# LED_matrix.net
KiCad netlist of a schematic drawn in EAGLE
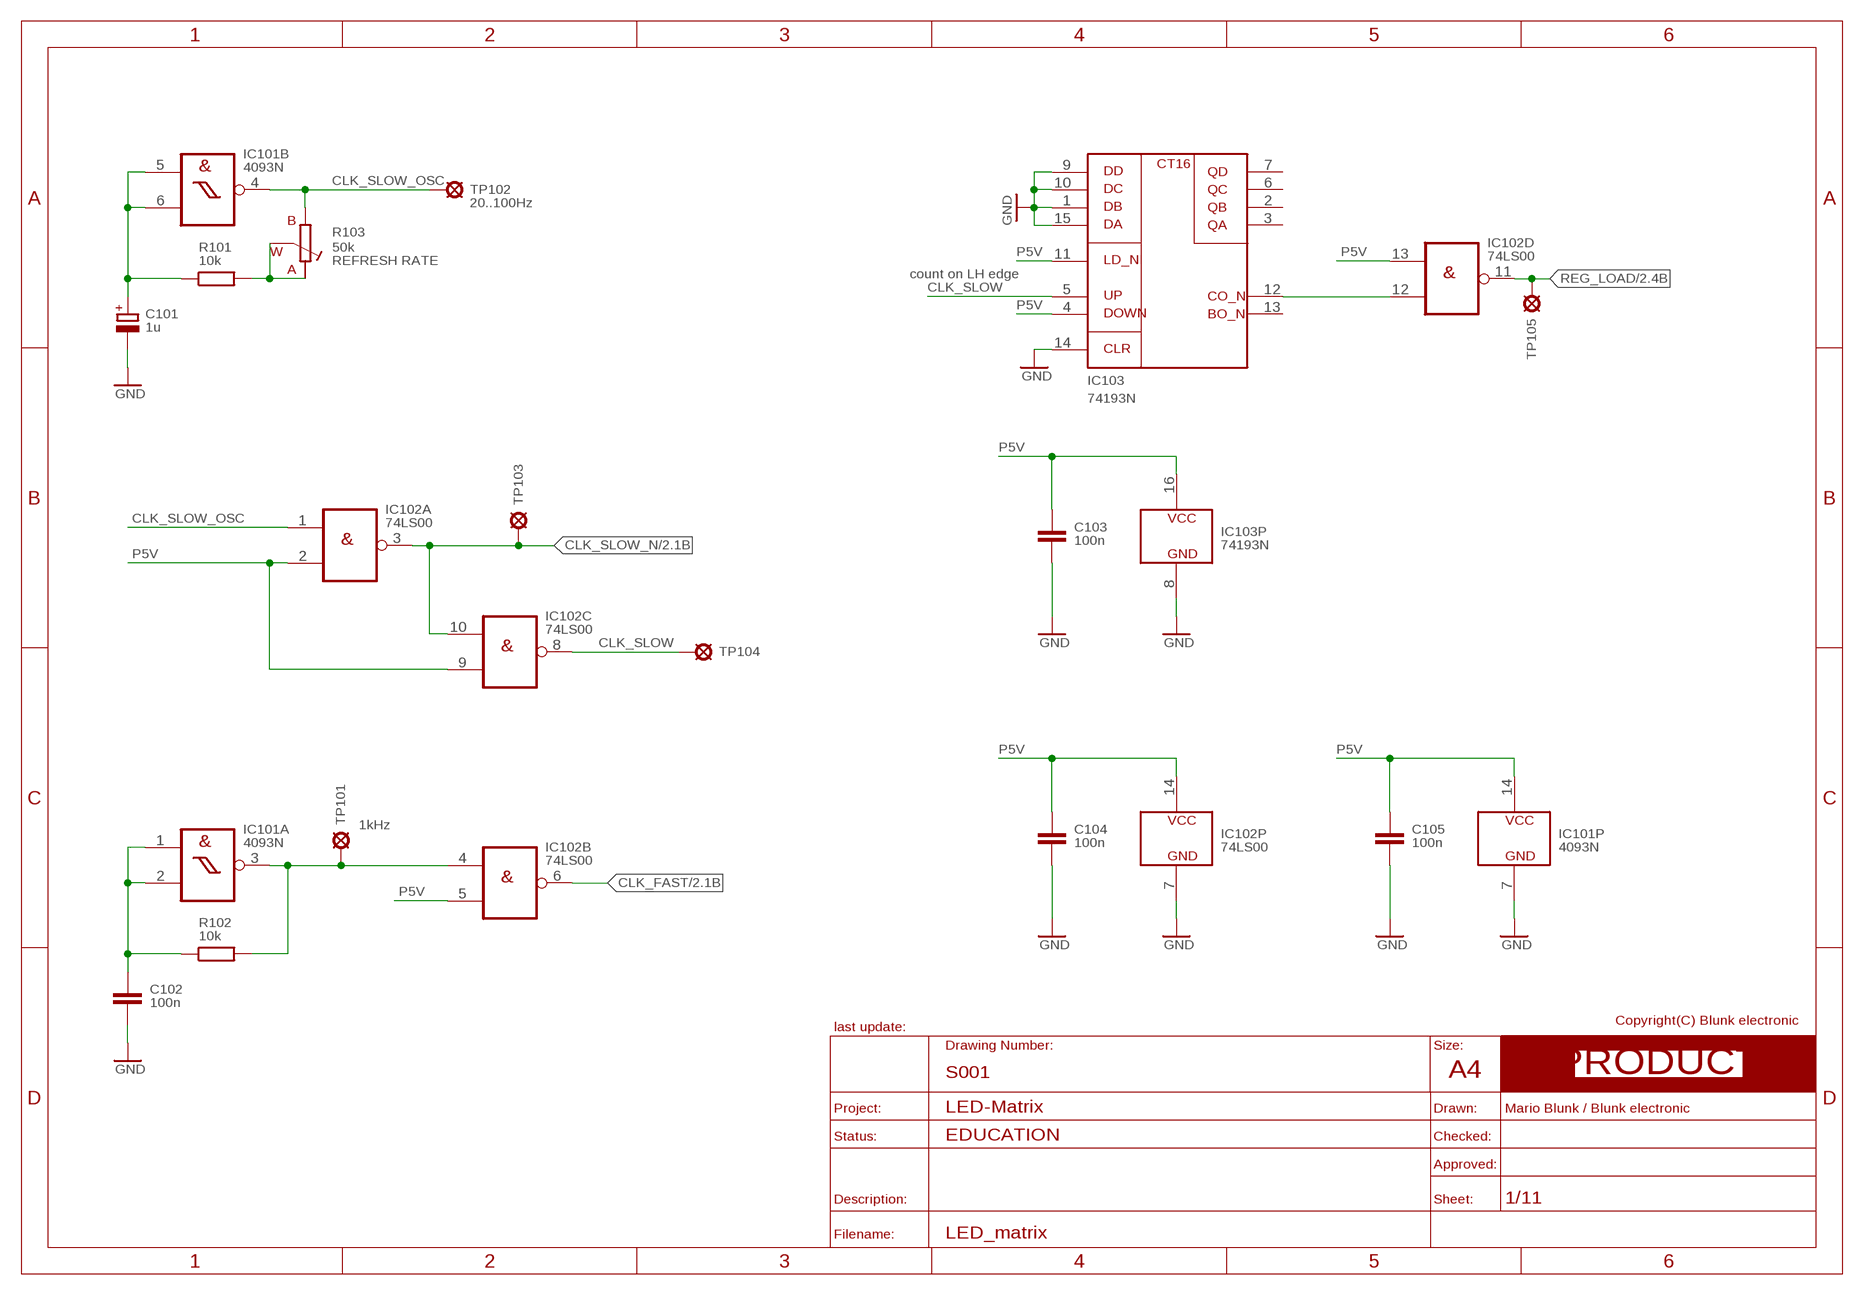
[diagram p0: schematic, sheet 1]
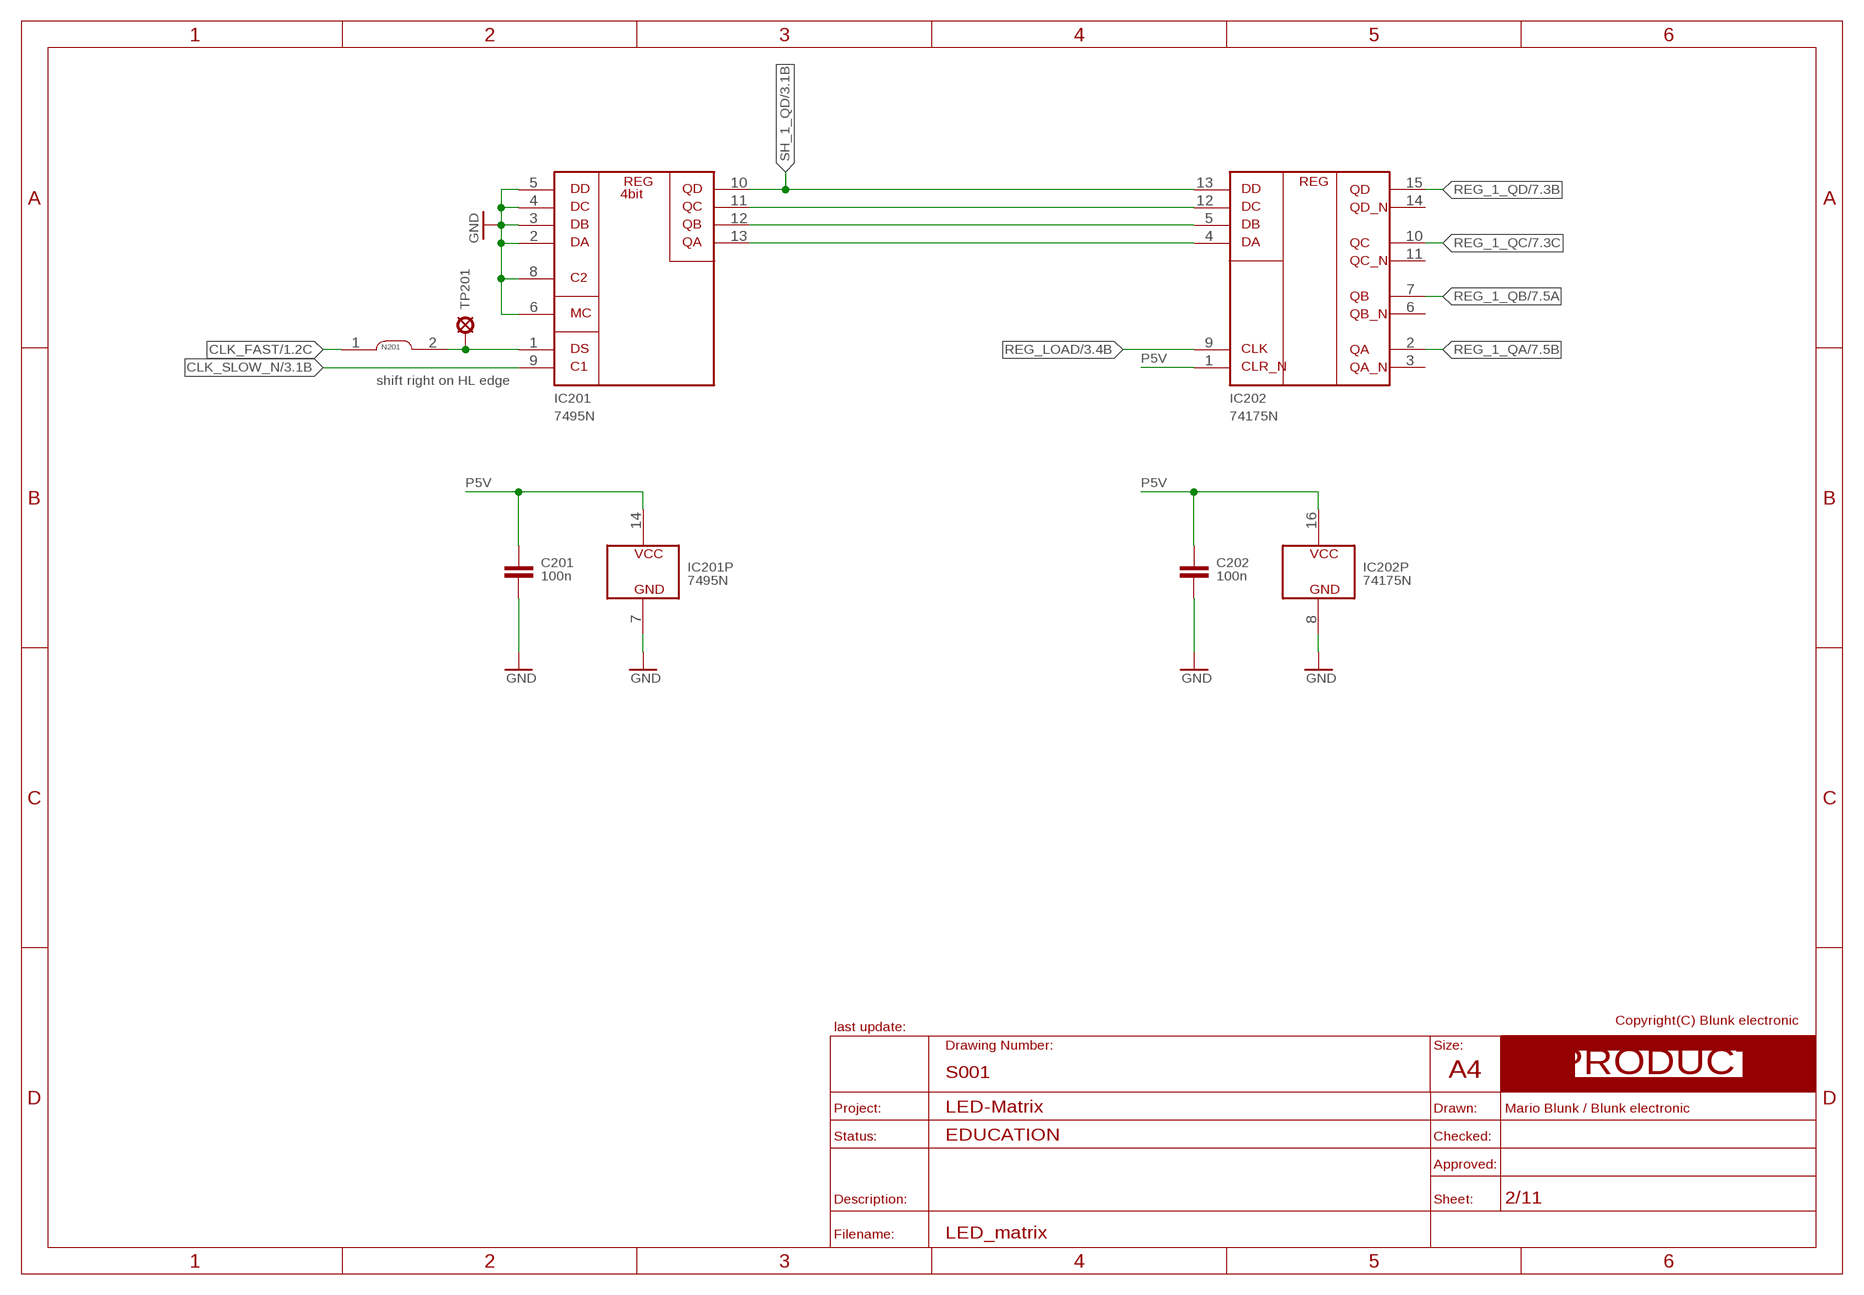
[diagram p1: schematic, sheet 2]
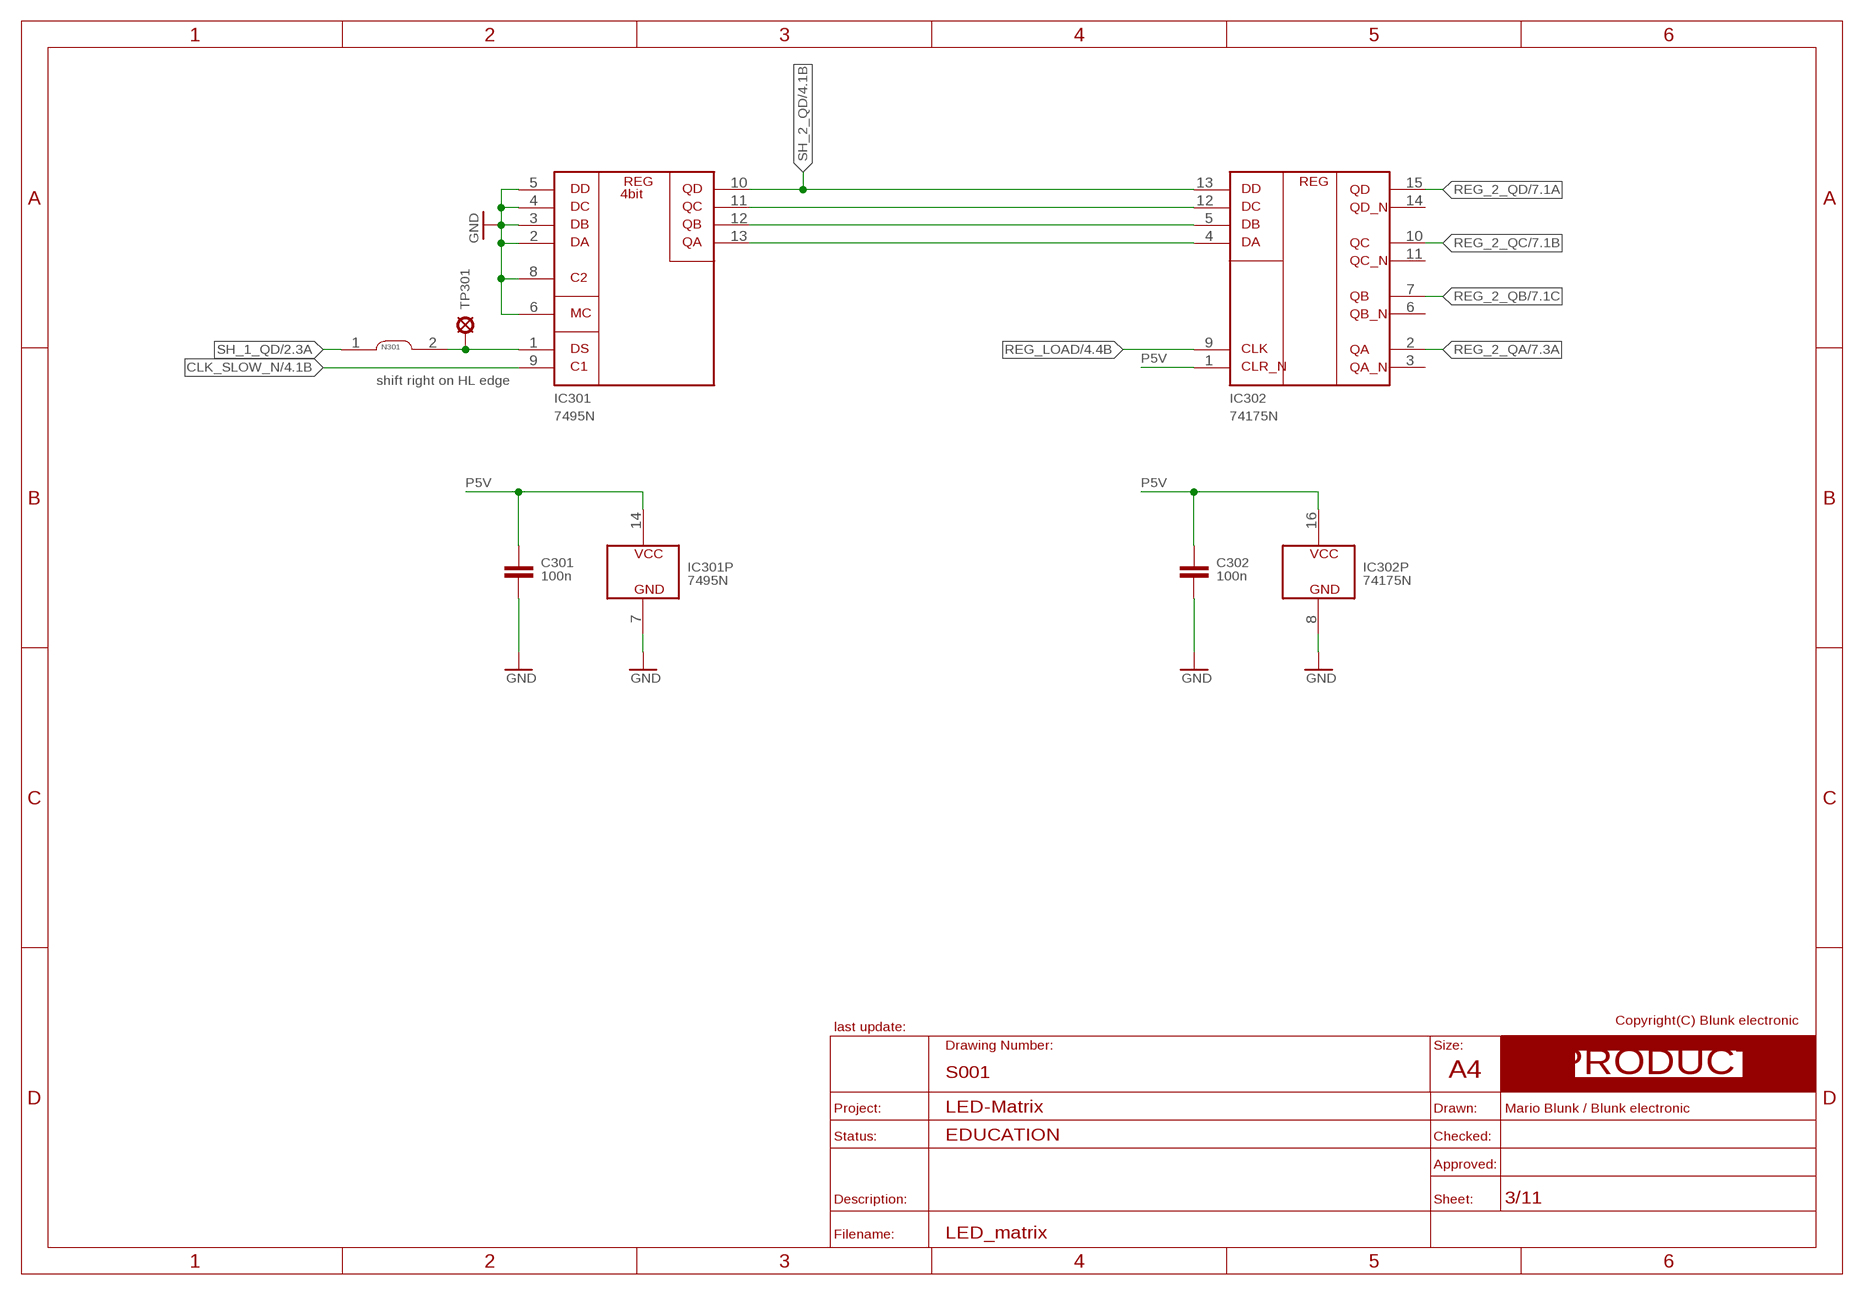
[diagram p2: schematic, sheet 3]
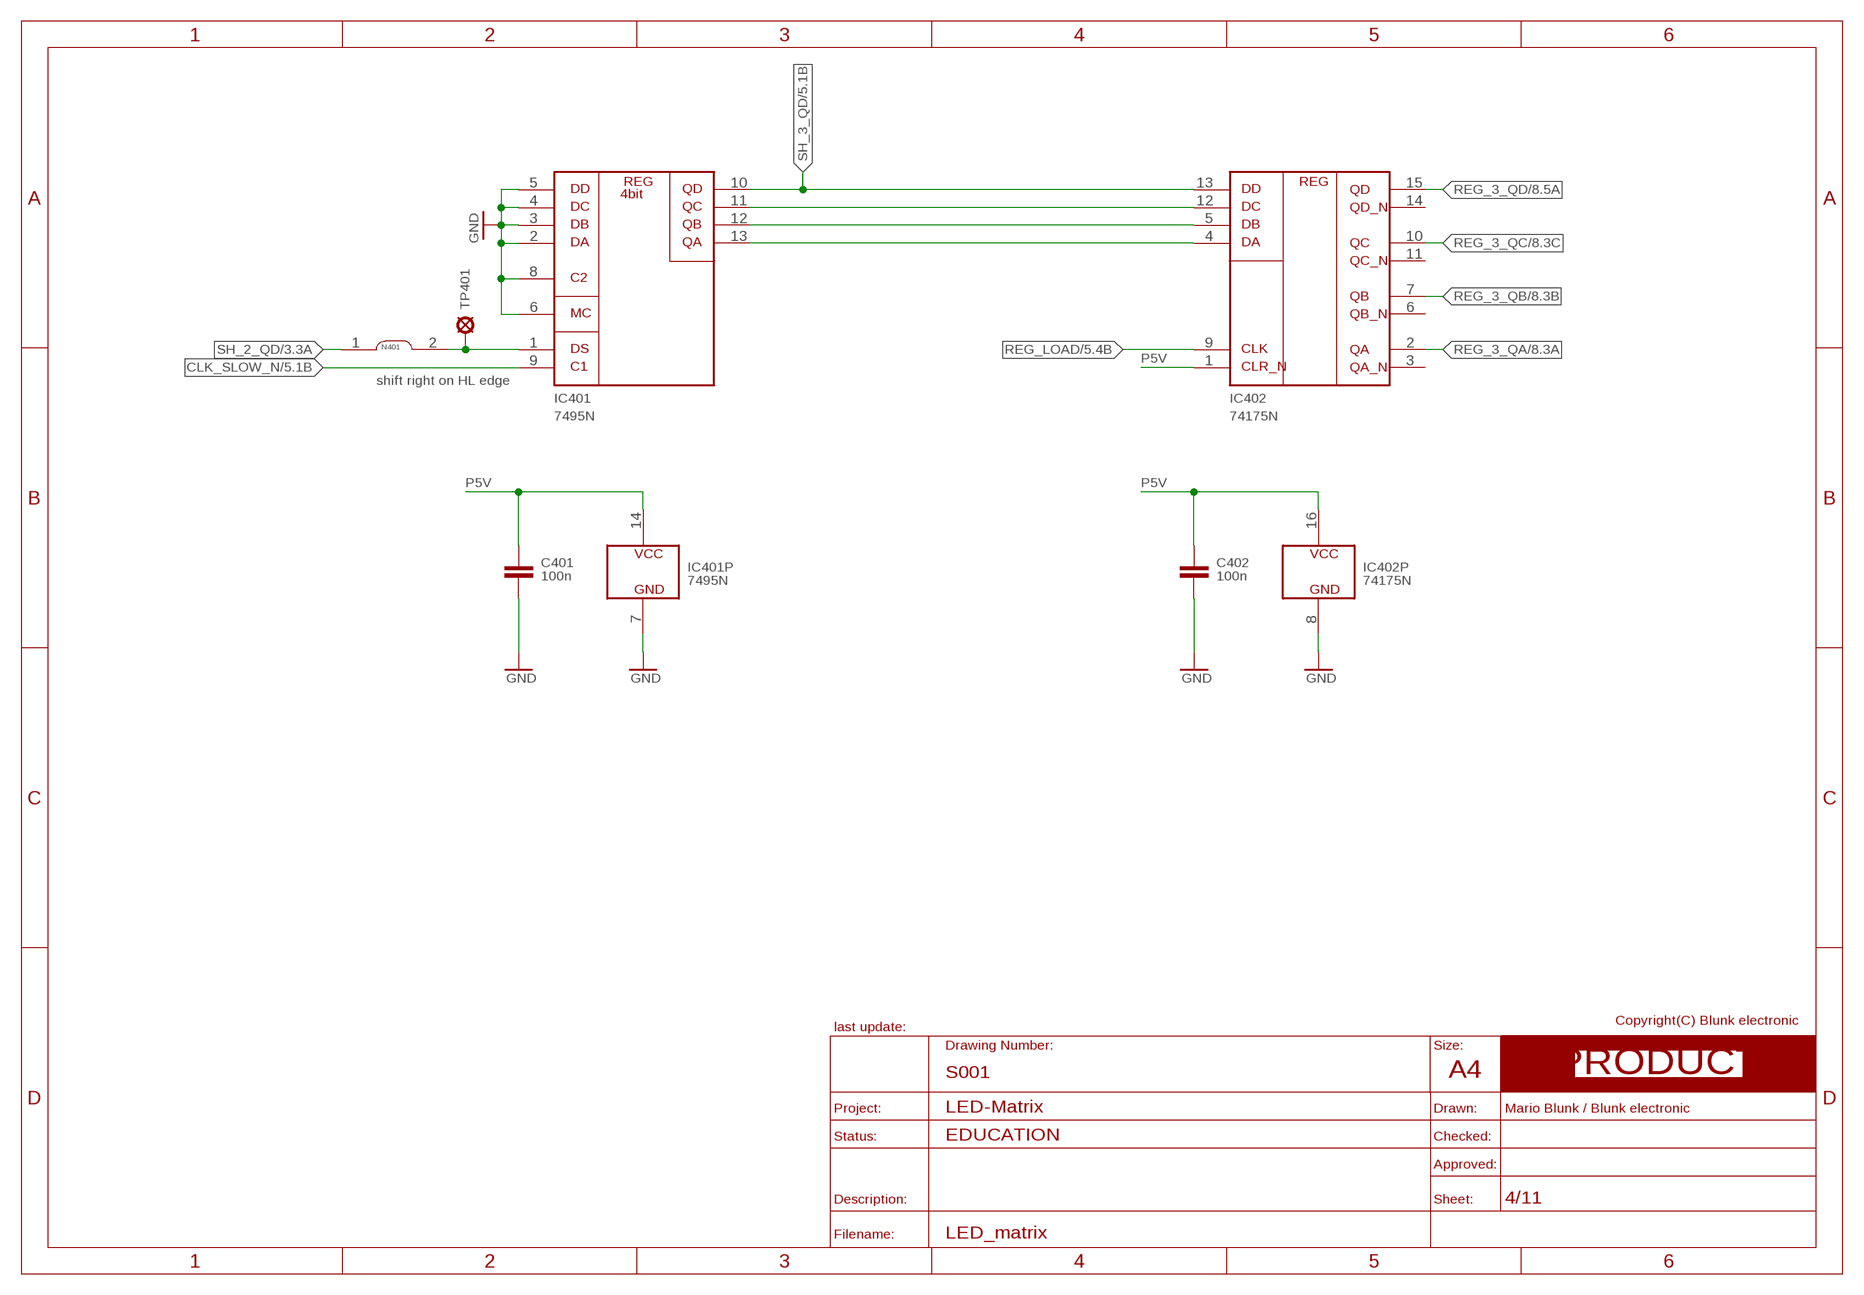
[diagram p3: schematic, sheet 4]
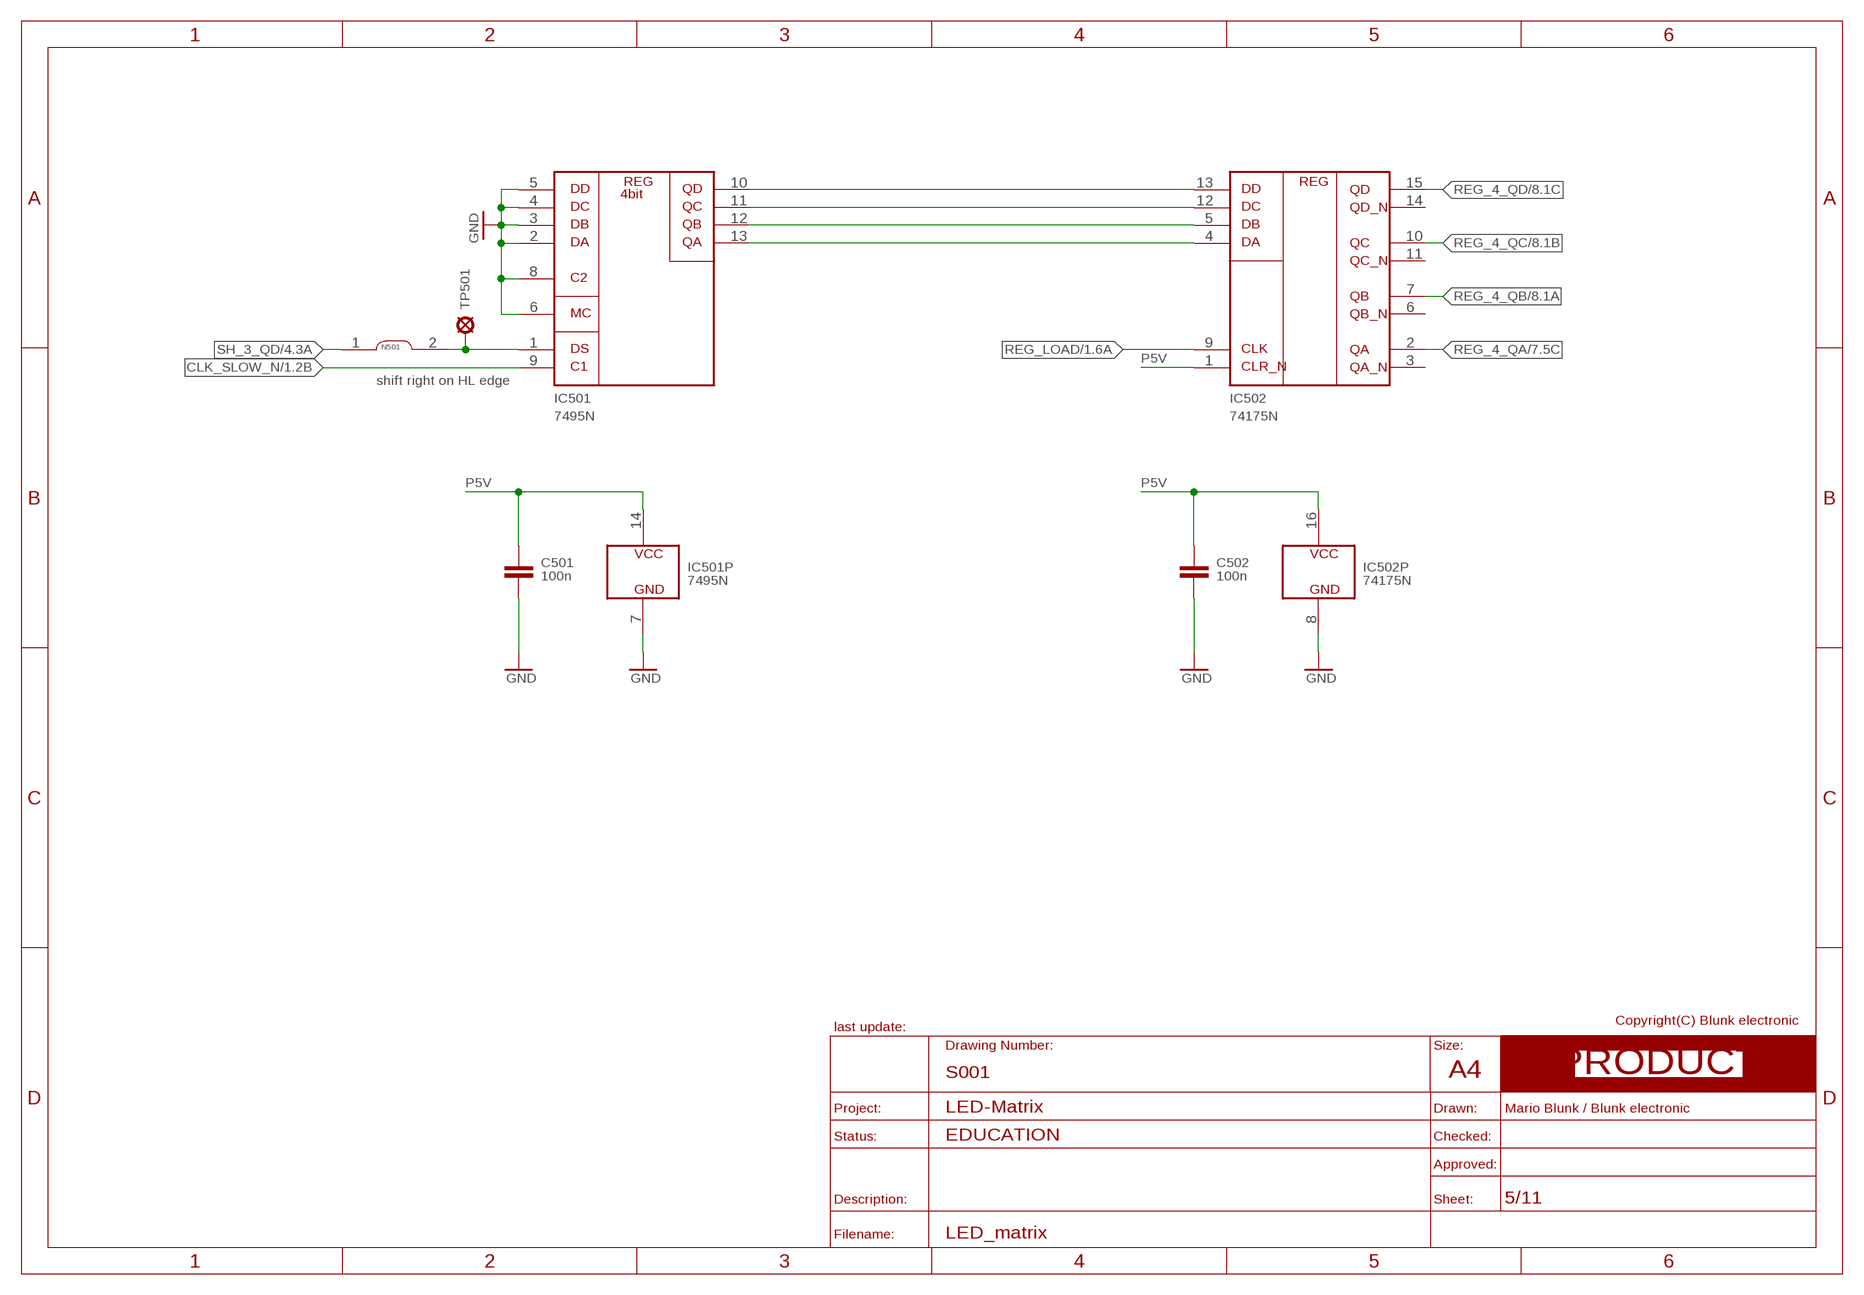
[diagram p4: schematic, sheet 5]
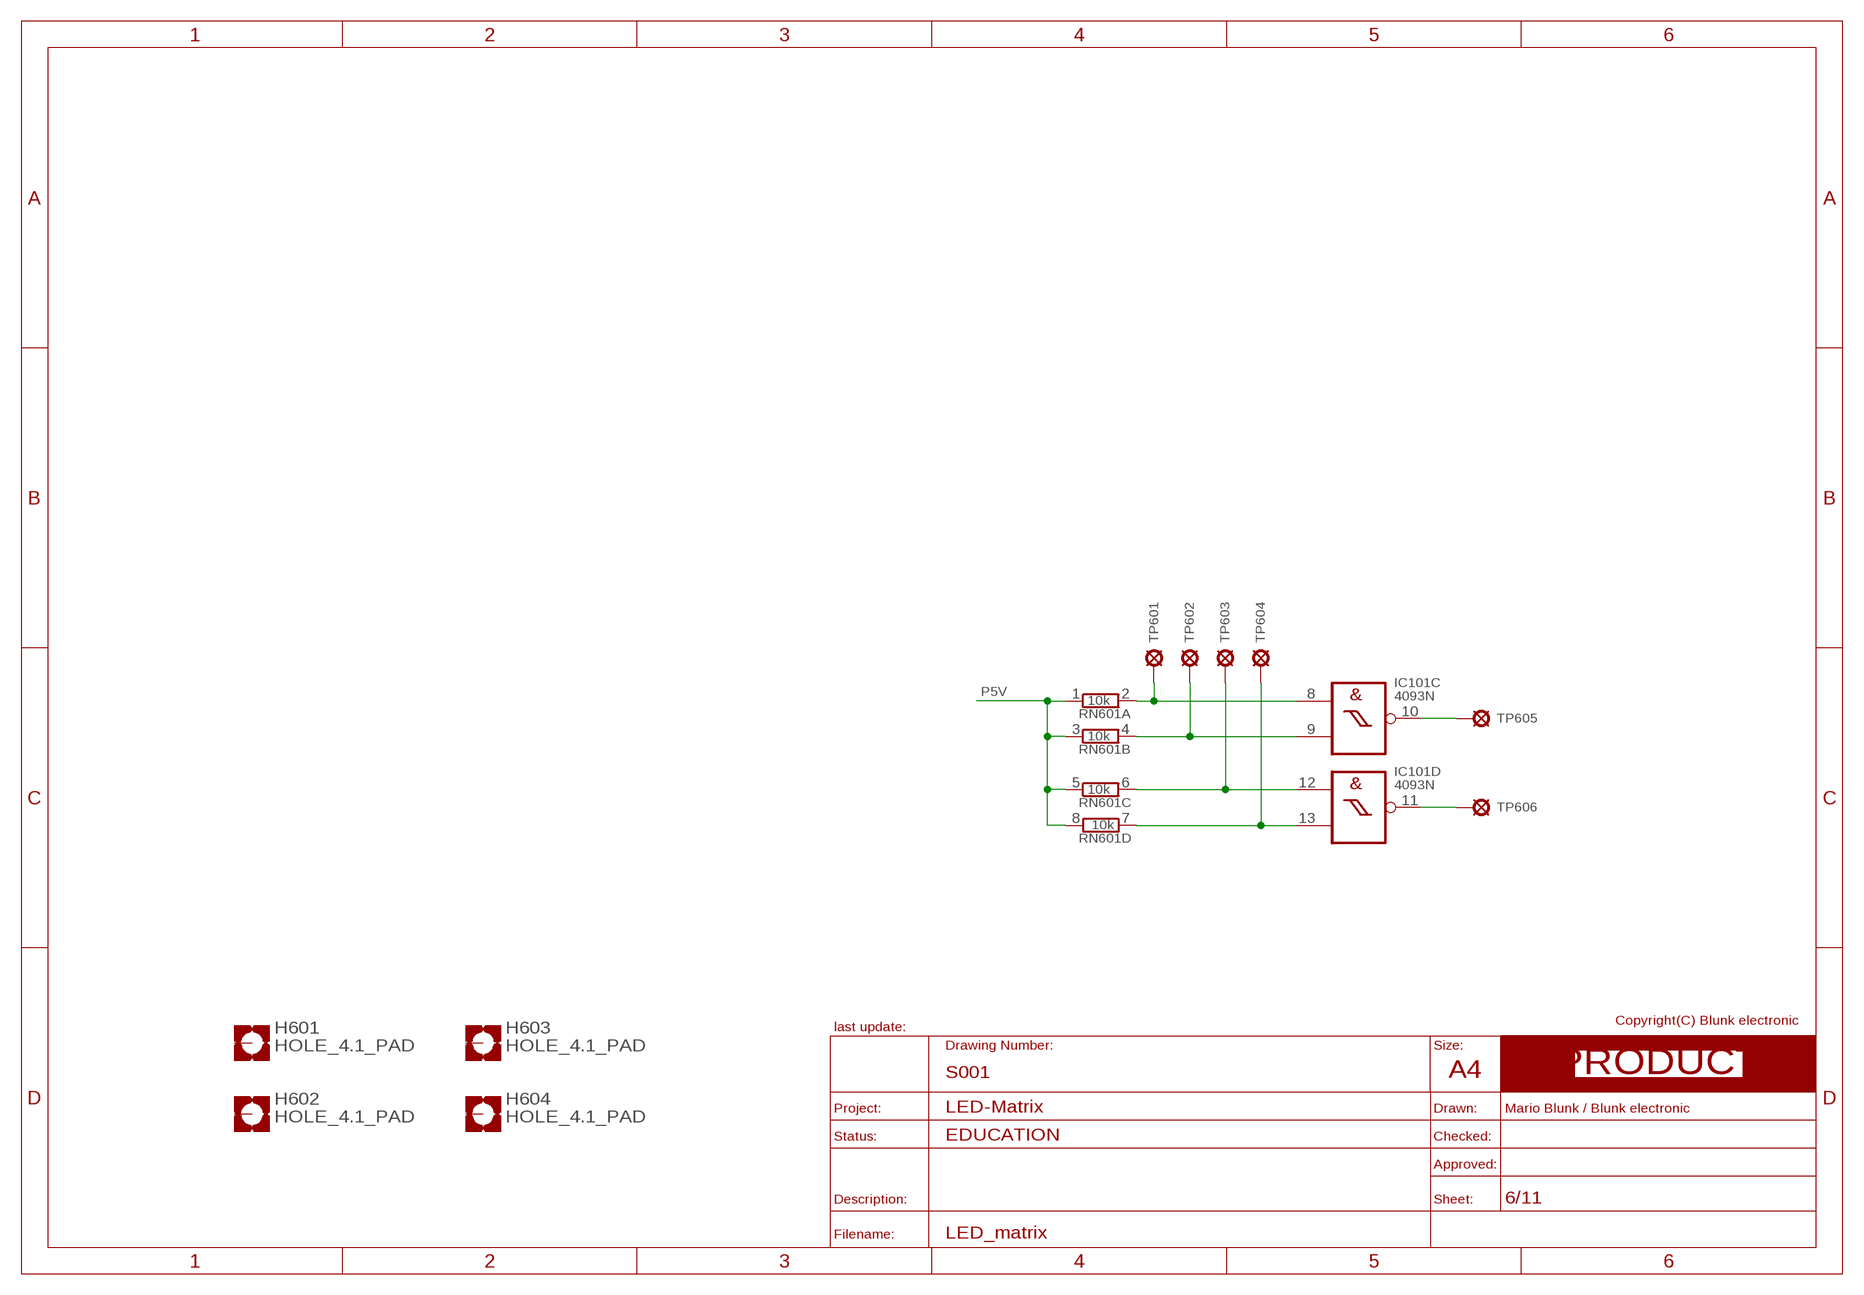
[diagram p5: schematic, sheet 6]
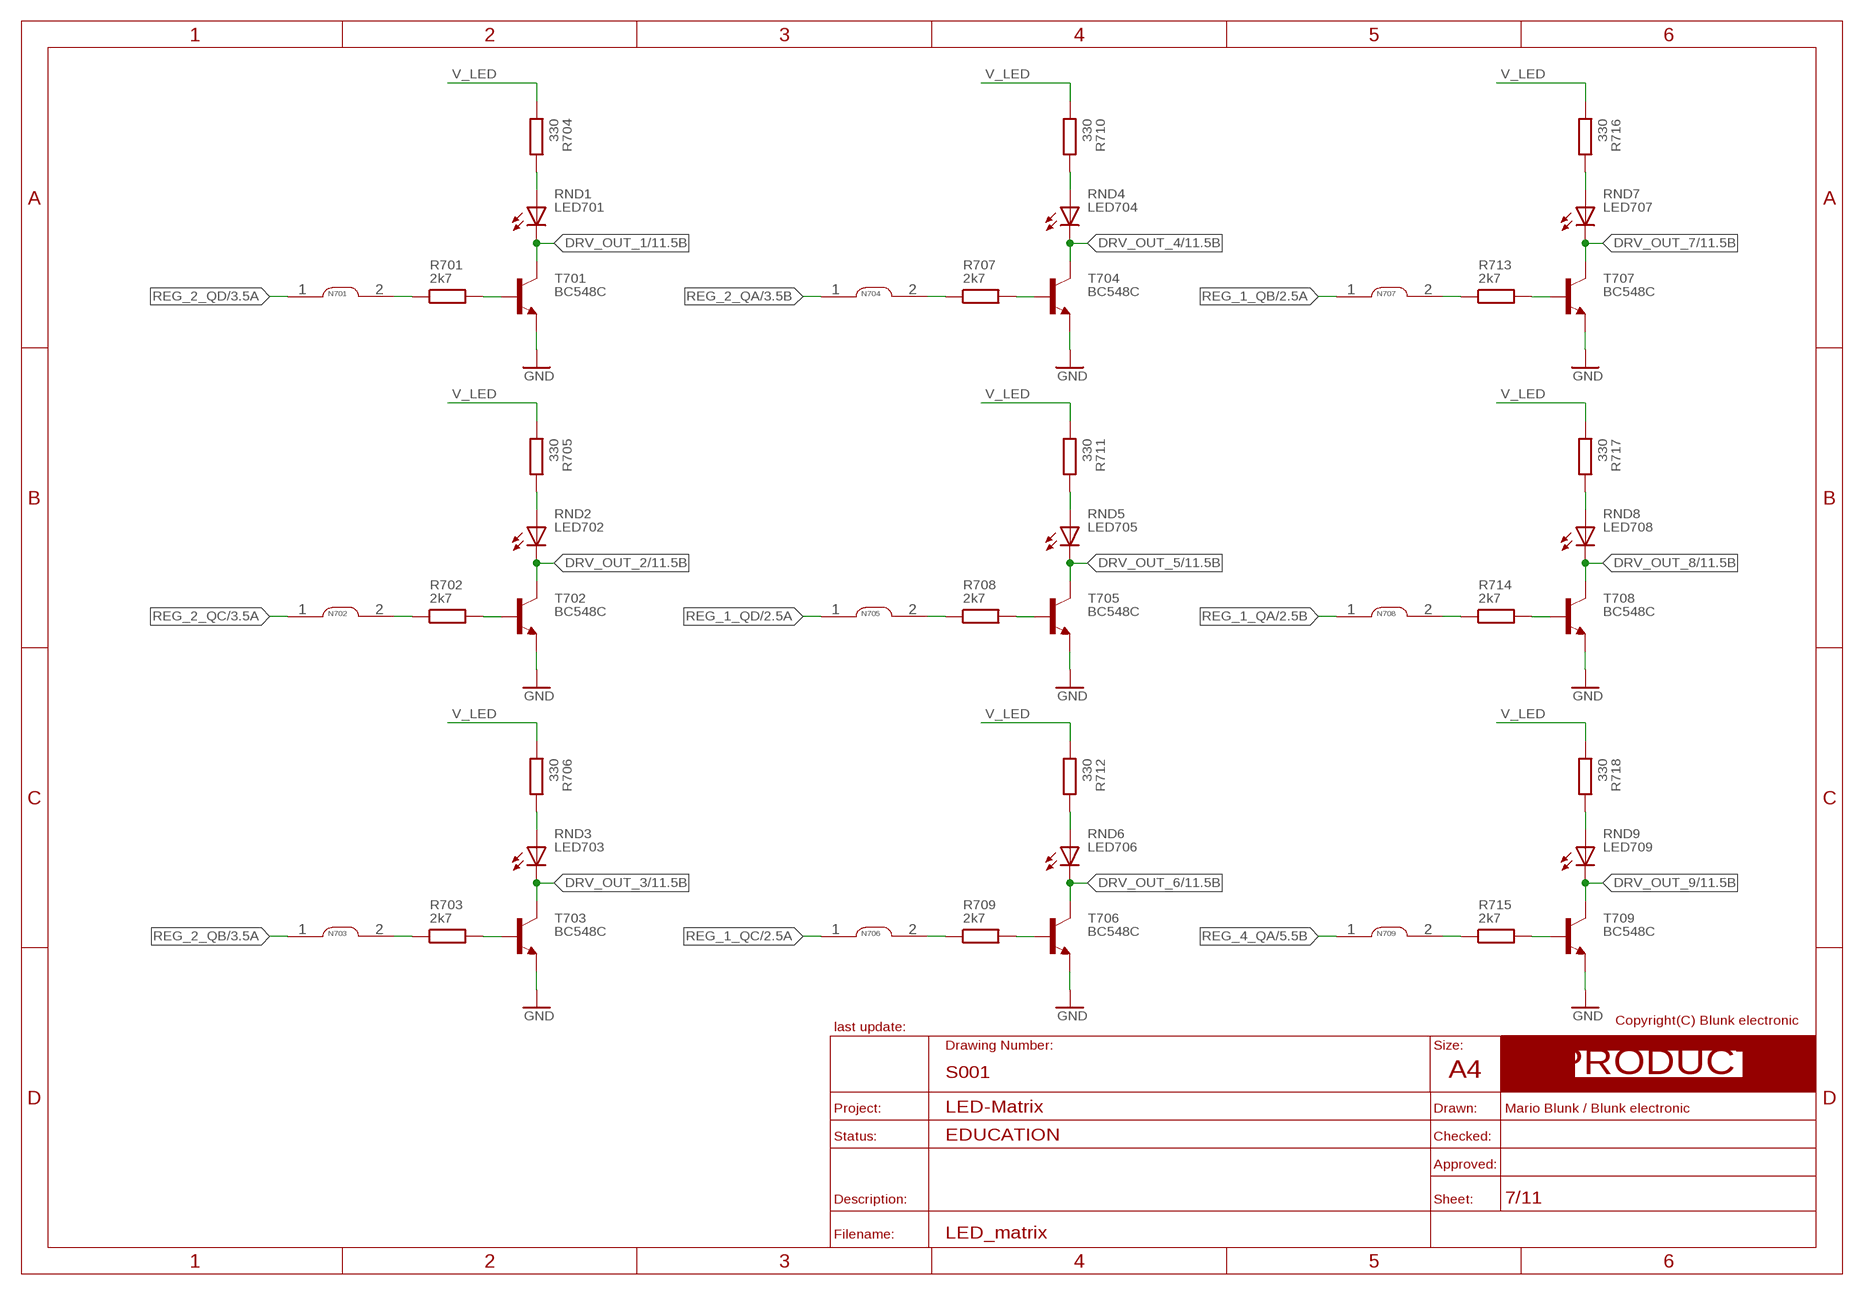
[diagram p6: schematic, sheet 7]
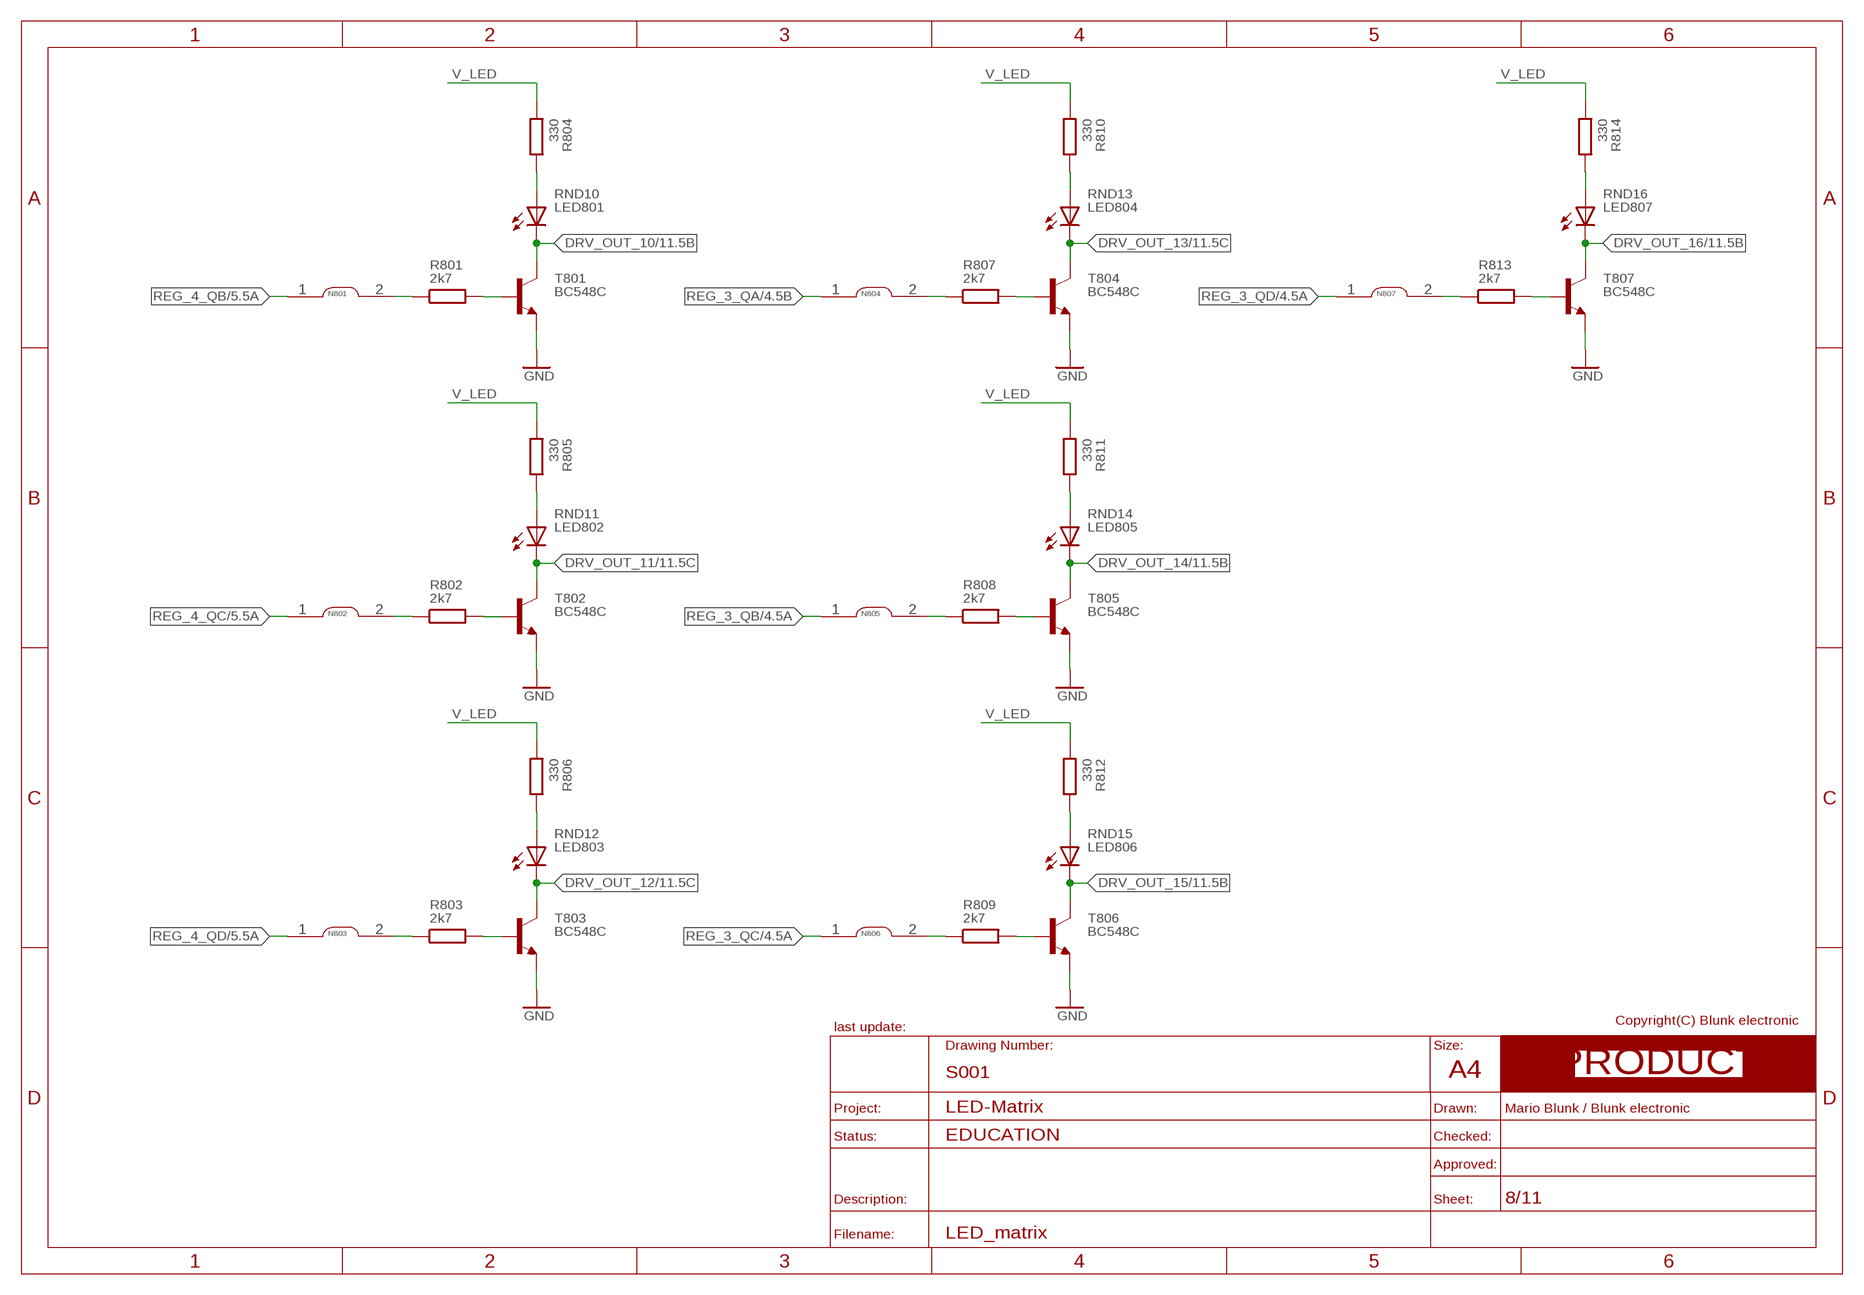
[diagram p7: schematic, sheet 8]
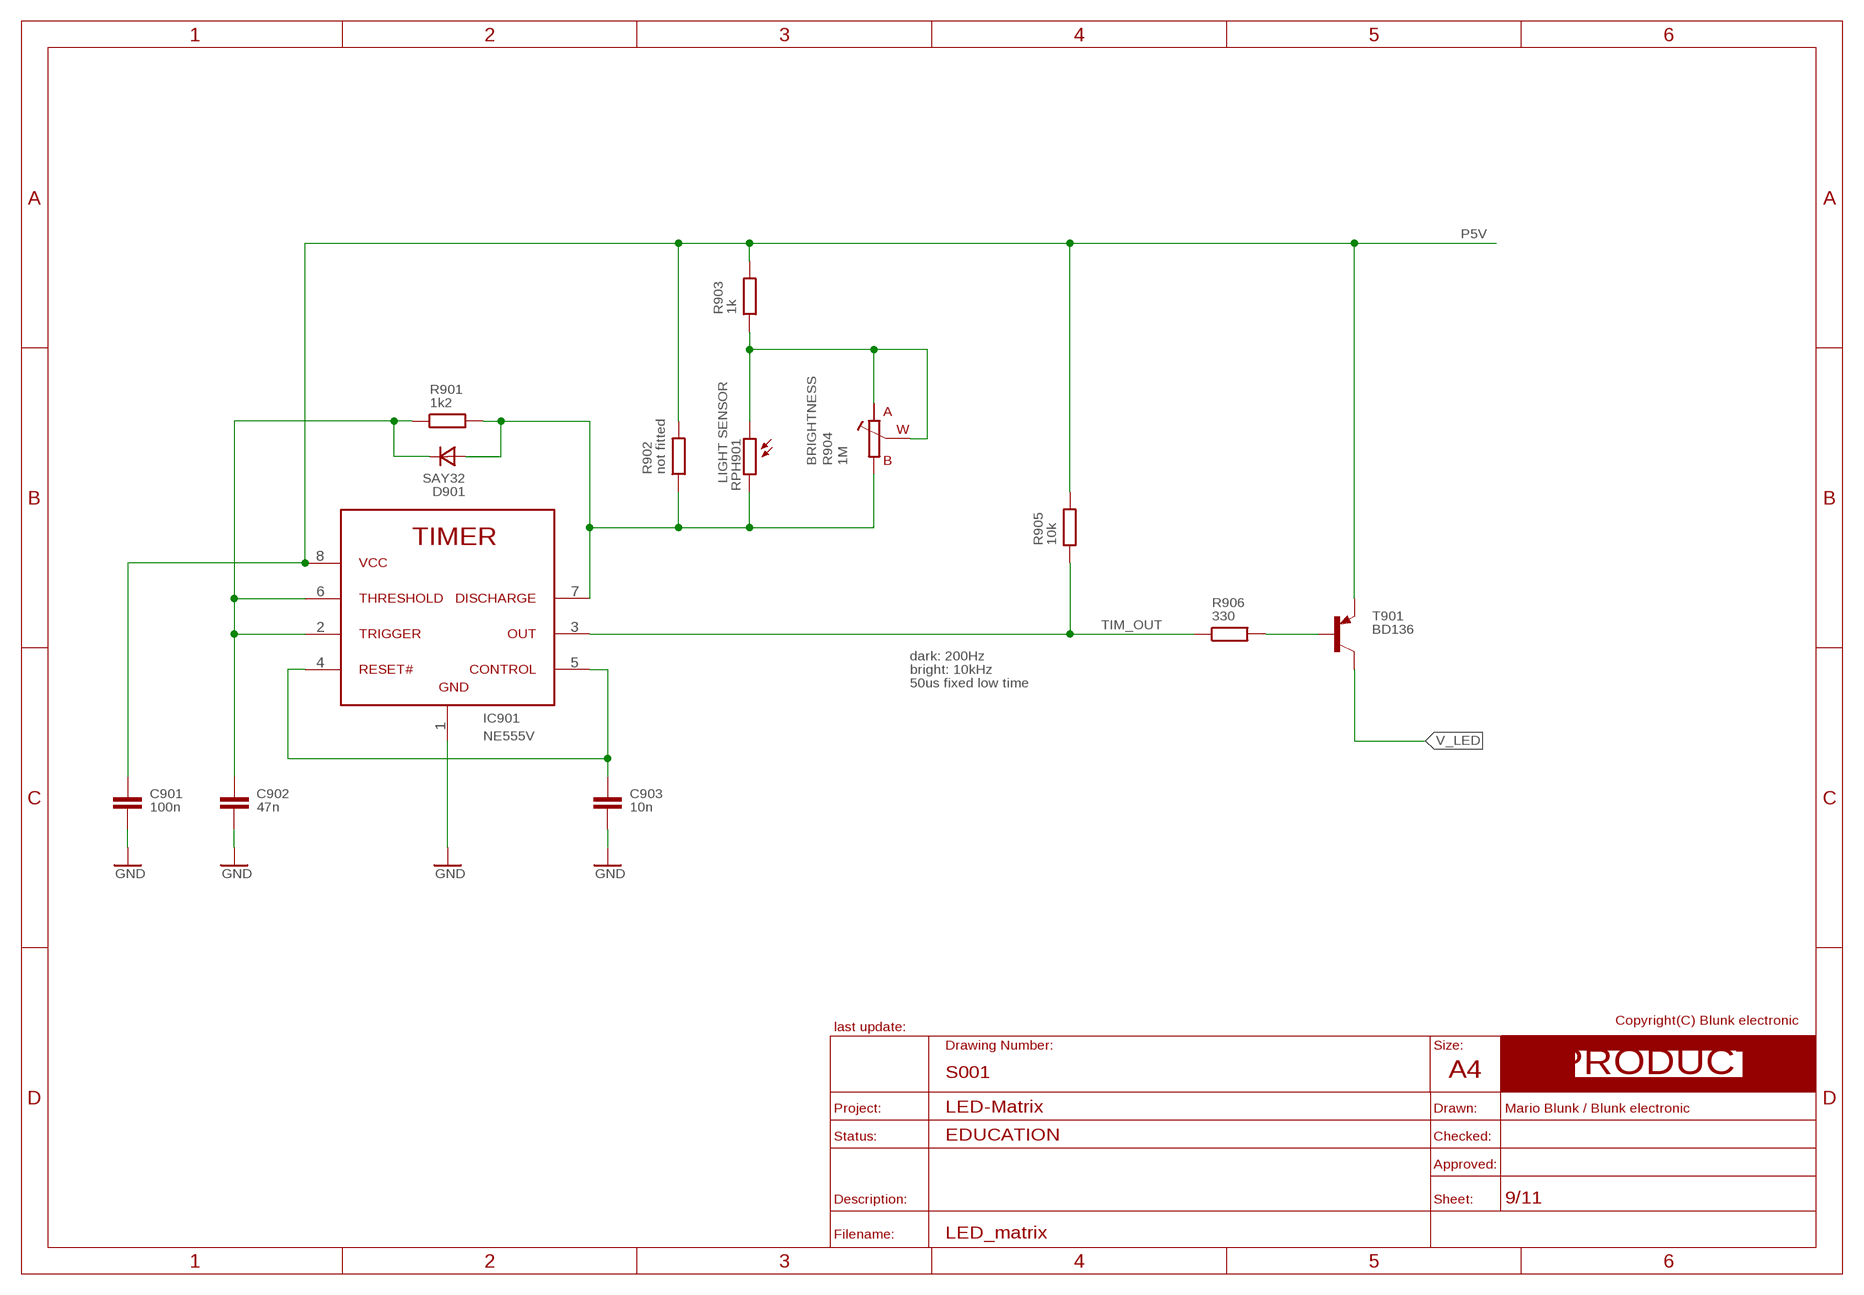
[diagram p8: schematic, sheet 9]
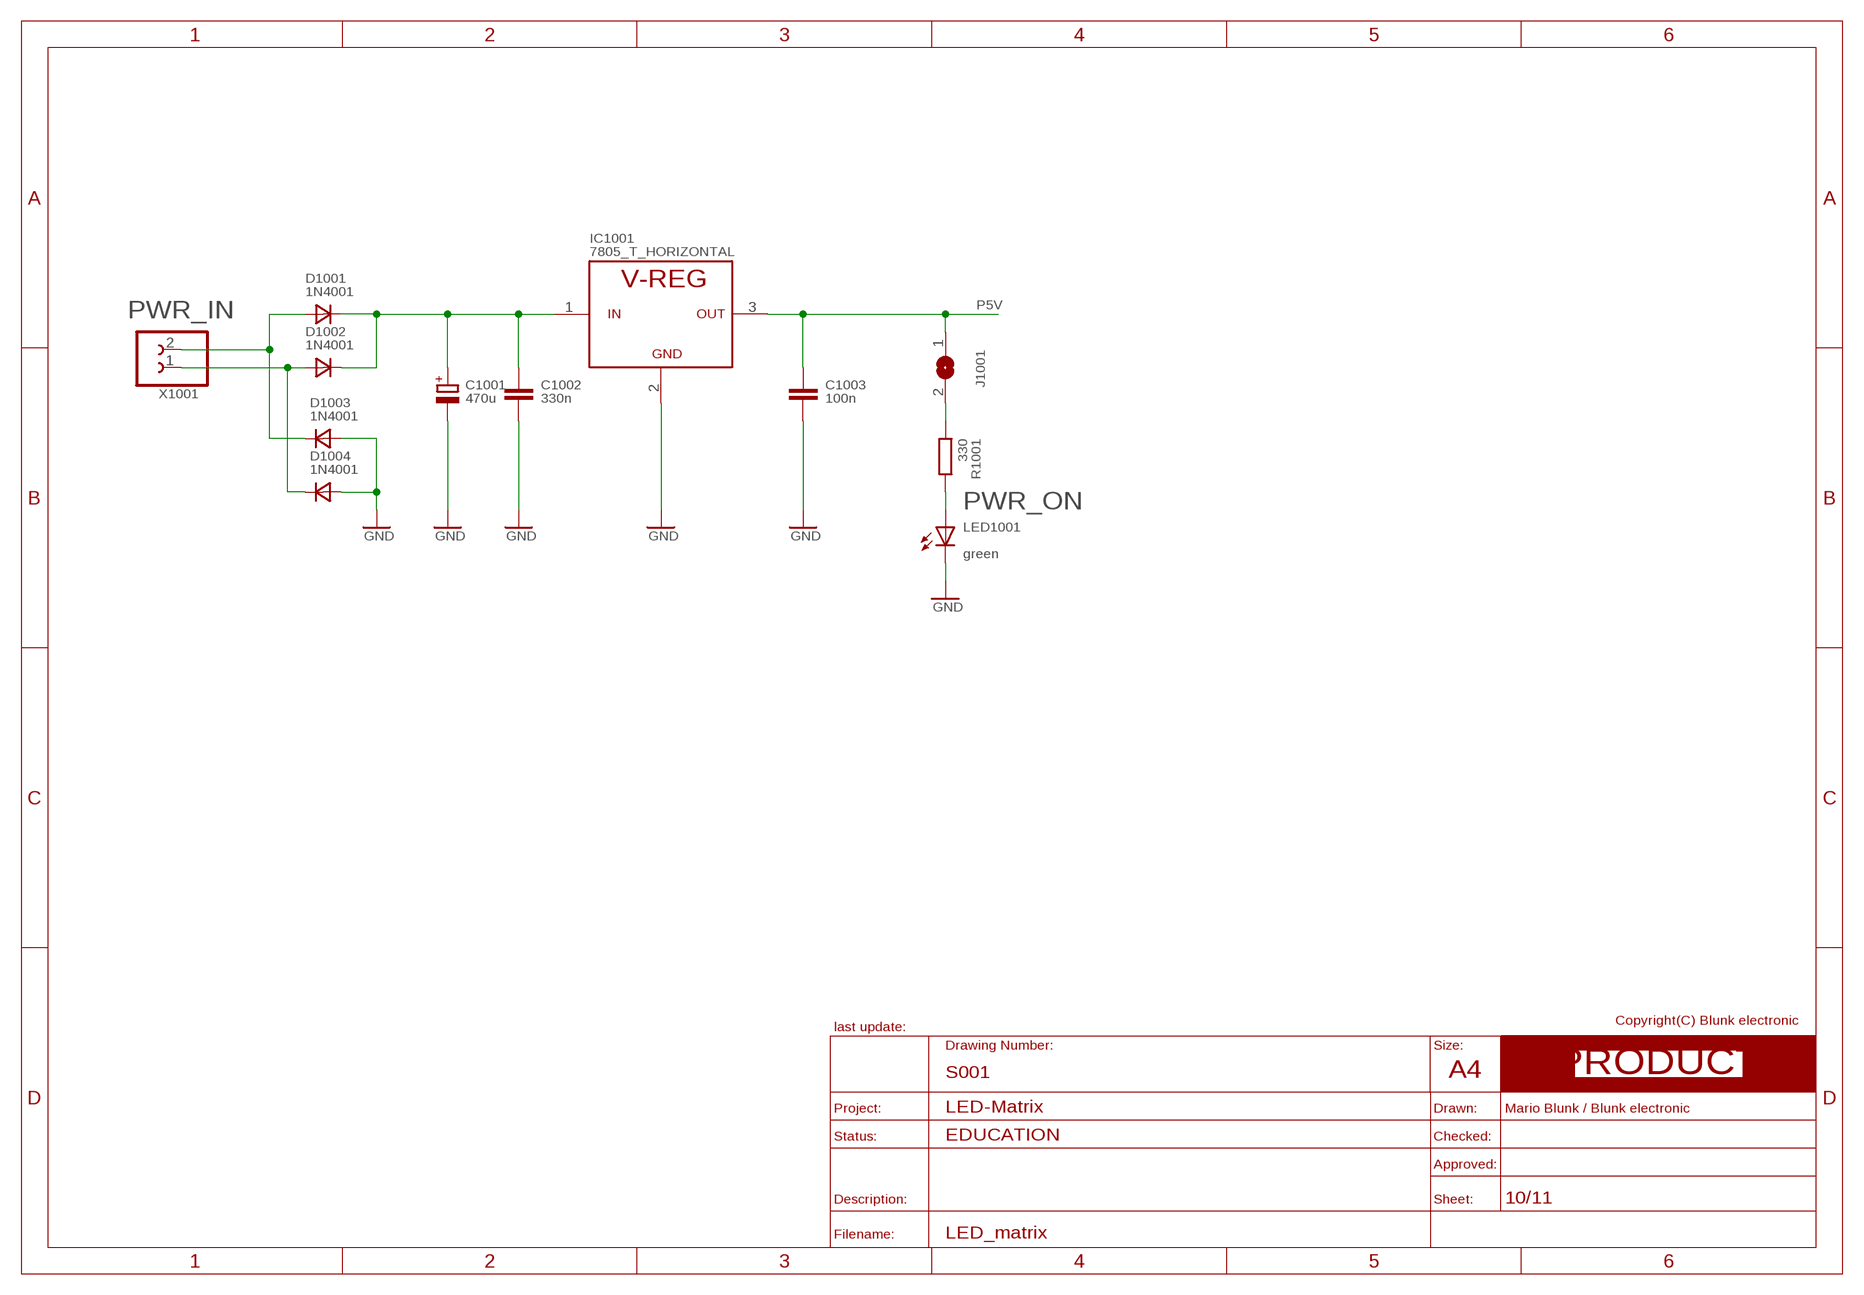
[diagram p9: schematic, sheet 10]
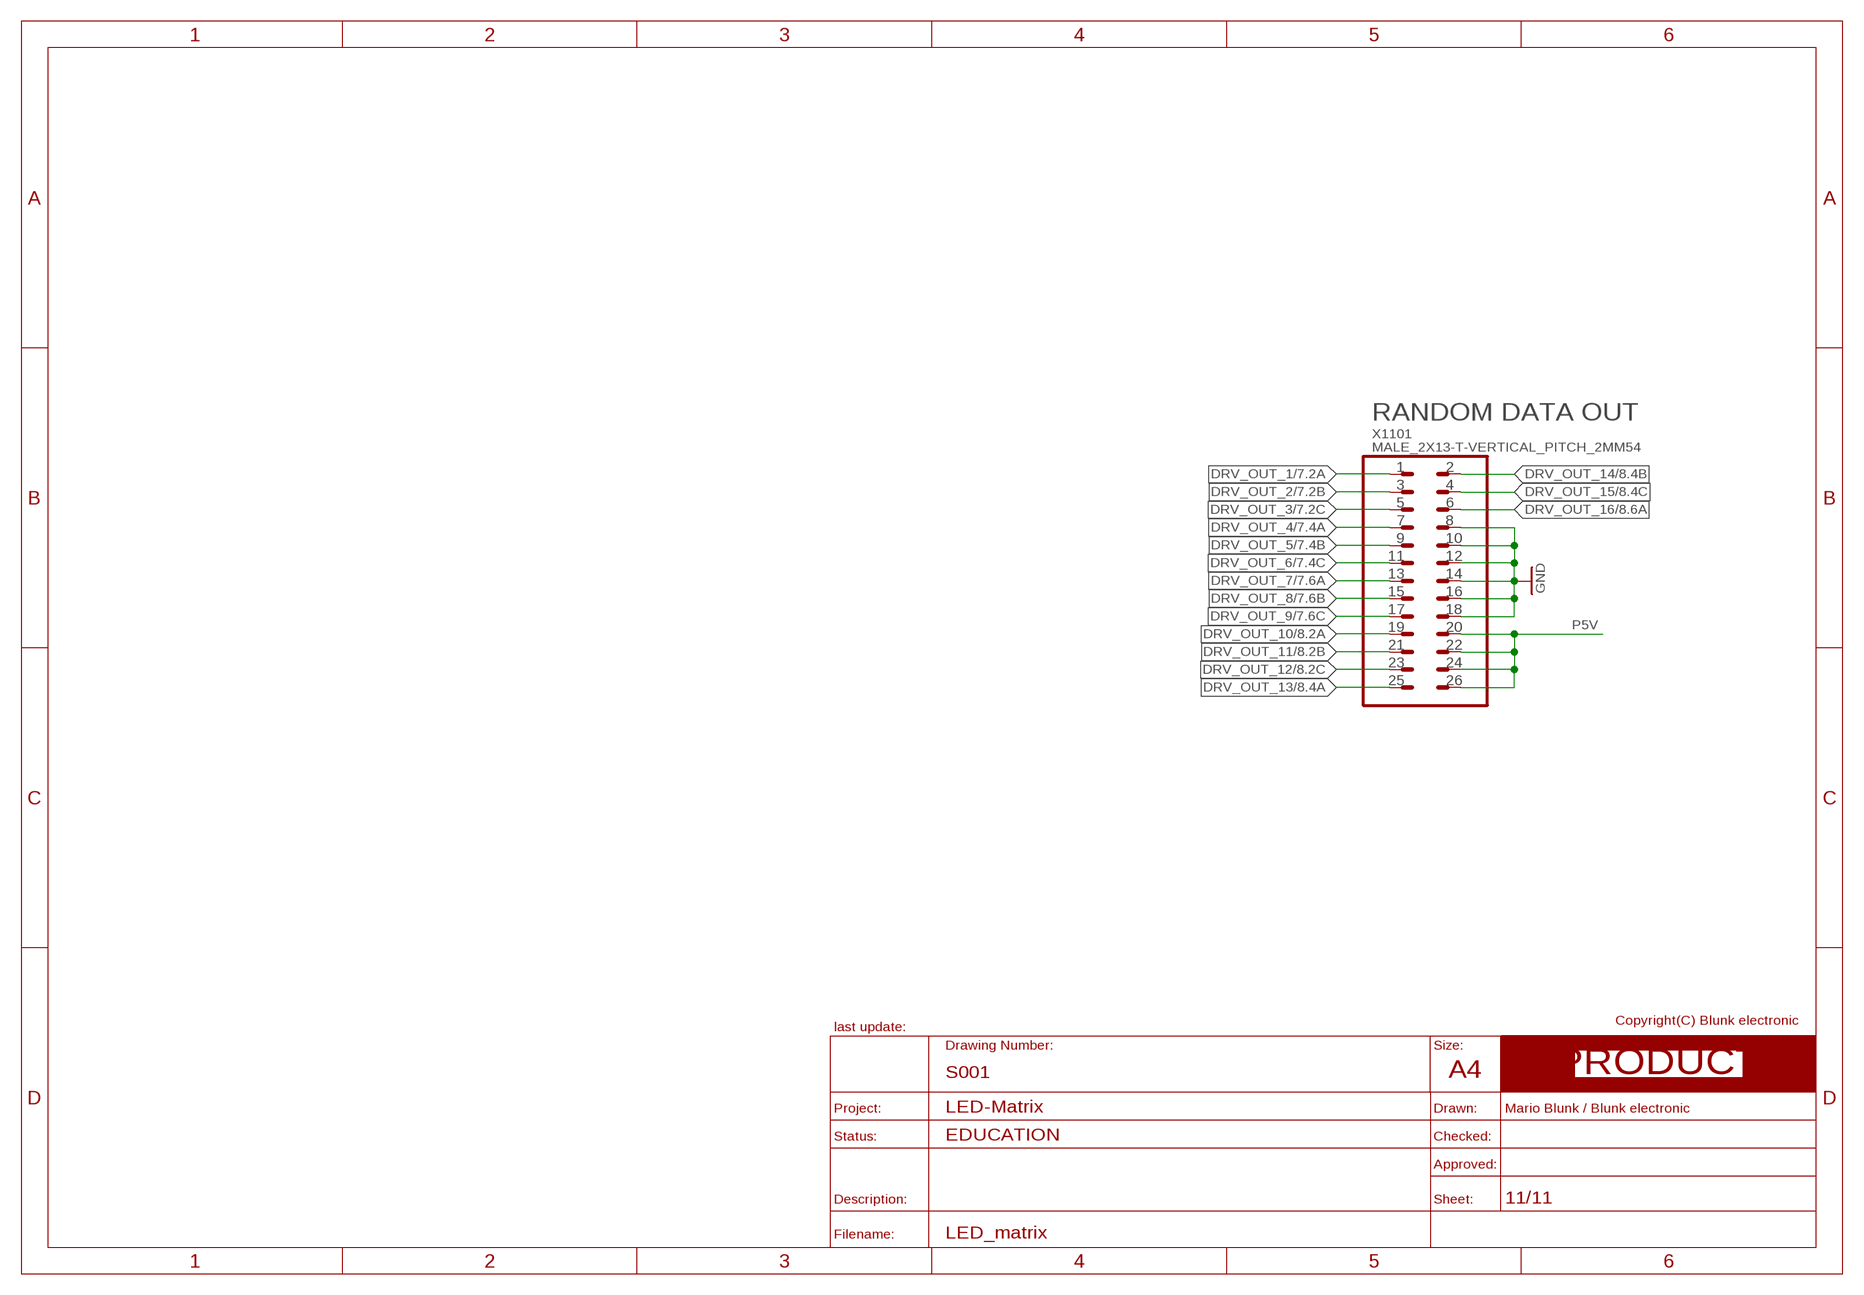
[diagram p10: schematic, sheet 11]

(export (version "E")
  (design (tool "Eeschema 10.0.6"))
  (components
    (comp (ref "C301")
      (value "100n")
      (footprint "eagle-import:T_DISC_4MM_PITCH_5MM")
      (fields (field (name "PART_CODE_BEL") "C_PAC_T_DISC_7mm_PITCH_5mm_VAL_100n"))
      (libsource (lib "eagle-import") (part "C_T_DISC_4MM_PITCH_5MM"))
    )
    (comp (ref "C302")
      (value "100n")
      (footprint "eagle-import:T_DISC_4MM_PITCH_5MM")
      (fields (field (name "PART_CODE_BEL") "C_PAC_T_DISC_7mm_PITCH_5mm_VAL_100n"))
      (libsource (lib "eagle-import") (part "C_T_DISC_4MM_PITCH_5MM"))
    )
    (comp (ref "IC301")
      (value "7495N")
      (footprint "eagle-import:T_NDIP14")
      (fields (field (name "PART_CODE_BEL") "IC_PAC_T_NDIP14_VAL_SN7495N"))
      (libsource (lib "eagle-import") (part "7495N"))
    )
    (comp (ref "IC302")
      (value "74175N")
      (footprint "eagle-import:T_NDIP16")
      (fields (field (name "PART_CODE_BEL") "IC_PAC_NDIP16_VAL_SN74175N"))
      (libsource (lib "eagle-import") (part "74175N"))
    )
    (comp (ref "N301")
      (value "NET_CHANGER-S-0.3MM")
      (footprint "eagle-import:S_NET_CHANGER_0.3MM")
      (libsource (lib "eagle-import") (part "NET_CHANGER-S-0.3MM"))
    )
    (comp (ref "TP301")
      (value "TEST_POINT_T_SMALL")
      (footprint "eagle-import:T_TEST_POINT_SMALL")
      (libsource (lib "eagle-import") (part "TEST_POINT_T_SMALL"))
    )
    (comp (ref "C101")
      (value "1u")
      (footprint "eagle-import:T_RADIAL_5MM_GRID_2.54MM")
      (fields (field (name "PART_CODE_BEL") "C_PAC_T_RADIAL_5mm_PITCH_2mm54_VAL_1u"))
      (libsource (lib "eagle-import") (part "C_POL_T_RAD5_GRID_2.54"))
    )
    (comp (ref "C102")
      (value "100n")
      (footprint "eagle-import:T_DISC_4MM_PITCH_5MM")
      (fields (field (name "PART_CODE_BEL") "C_PAC_T_DISC_7mm_PITCH_5mm_VAL_100n"))
      (libsource (lib "eagle-import") (part "C_T_DISC_4MM_PITCH_5MM"))
    )
    (comp (ref "C103")
      (value "100n")
      (footprint "eagle-import:T_DISC_4MM_PITCH_5MM")
      (fields (field (name "PART_CODE_BEL") "C_PAC_T_DISC_7mm_PITCH_5mm_VAL_100n"))
      (libsource (lib "eagle-import") (part "C_T_DISC_4MM_PITCH_5MM"))
    )
    (comp (ref "C104")
      (value "100n")
      (footprint "eagle-import:T_DISC_4MM_PITCH_5MM")
      (fields (field (name "PART_CODE_BEL") "C_PAC_T_DISC_7mm_PITCH_5mm_VAL_100n"))
      (libsource (lib "eagle-import") (part "C_T_DISC_4MM_PITCH_5MM"))
    )
    (comp (ref "C105")
      (value "100n")
      (footprint "eagle-import:T_DISC_4MM_PITCH_5MM")
      (fields (field (name "PART_CODE_BEL") "C_PAC_T_DISC_7mm_PITCH_5mm_VAL_100n"))
      (libsource (lib "eagle-import") (part "C_T_DISC_4MM_PITCH_5MM"))
    )
    (comp (ref "IC101")
      (value "4093N")
      (footprint "eagle-import:T_NDIP14")
      (libsource (lib "eagle-import") (part "4093N"))
    )
    (comp (ref "IC102")
      (value "74LS00")
      (footprint "eagle-import:T_NDIP14")
      (fields (field (name "PART_CODE_BEL") "IC_PAC_T_NDIP14_VAL_SN74LS00N"))
      (libsource (lib "eagle-import") (part "7400N"))
    )
    (comp (ref "IC103")
      (value "74193N")
      (footprint "eagle-import:T_NDIP16")
      (fields (field (name "PART_CODE_BEL") "IC_PAC_NDIP16_VAL_SN74193N"))
      (libsource (lib "eagle-import") (part "74193N"))
    )
    (comp (ref "R101")
      (value "10k")
      (footprint "eagle-import:T_0207_PITCH_10MM")
      (fields (field (name "PART_CODE_BEL") "R_PAC_T_0207_PITCH_10mm_VAL_10k"))
      (libsource (lib "eagle-import") (part "R_T_0207_PITCH_10MM"))
    )
    (comp (ref "R102")
      (value "10k")
      (footprint "eagle-import:T_0207_PITCH_10MM")
      (fields (field (name "PART_CODE_BEL") "R_PAC_T_0207_PITCH_10mm_VAL_10k"))
      (libsource (lib "eagle-import") (part "R_T_0207_PITCH_10MM"))
    )
    (comp (ref "R103")
      (value "50k")
      (footprint "eagle-import:T_TRIM_PIHER_PT10_HORIZONTAL")
      (fields
        (field (name "FUNCTION") "REFRESH RATE")
        (field (name "PART_CODE_BEL") "R_PAC_T_TRIM_PIHER_PT10_HORIZONTAL_VAL_50k")
      )
      (libsource (lib "eagle-import") (part "RA_T_PT10_HORIZONTAL"))
    )
    (comp (ref "TP101")
      (value "TEST_POINT_T_SMALL")
      (footprint "eagle-import:T_TEST_POINT_SMALL")
      (libsource (lib "eagle-import") (part "TEST_POINT_T_SMALL"))
    )
    (comp (ref "TP102")
      (value "TEST_POINT_T_SMALL")
      (footprint "eagle-import:T_TEST_POINT_SMALL")
      (libsource (lib "eagle-import") (part "TEST_POINT_T_SMALL"))
    )
    (comp (ref "TP103")
      (value "TEST_POINT_T_SMALL")
      (footprint "eagle-import:T_TEST_POINT_SMALL")
      (libsource (lib "eagle-import") (part "TEST_POINT_T_SMALL"))
    )
    (comp (ref "TP104")
      (value "TEST_POINT_T_SMALL")
      (footprint "eagle-import:T_TEST_POINT_SMALL")
      (libsource (lib "eagle-import") (part "TEST_POINT_T_SMALL"))
    )
    (comp (ref "TP105")
      (value "TEST_POINT_T_SMALL")
      (footprint "eagle-import:T_TEST_POINT_SMALL")
      (libsource (lib "eagle-import") (part "TEST_POINT_T_SMALL"))
    )
    (comp (ref "LED701")
      (value "LED_T_ROUND_3MM")
      (footprint "eagle-import:T_ROUND_3MM")
      (fields (field (name "FUNCTION") "RND1"))
      (libsource (lib "eagle-import") (part "LED_T_ROUND_3MM"))
    )
    (comp (ref "LED702")
      (value "LED_T_ROUND_3MM")
      (footprint "eagle-import:T_ROUND_3MM")
      (fields (field (name "PURPOSE") "RND2"))
      (libsource (lib "eagle-import") (part "LED_T_ROUND_3MM"))
    )
    (comp (ref "LED703")
      (value "LED_T_ROUND_3MM")
      (footprint "eagle-import:T_ROUND_3MM")
      (fields (field (name "PURPOSE") "RND3"))
      (libsource (lib "eagle-import") (part "LED_T_ROUND_3MM"))
    )
    (comp (ref "LED704")
      (value "LED_T_ROUND_3MM")
      (footprint "eagle-import:T_ROUND_3MM")
      (fields (field (name "PURPOSE") "RND4"))
      (libsource (lib "eagle-import") (part "LED_T_ROUND_3MM"))
    )
    (comp (ref "LED705")
      (value "LED_T_ROUND_3MM")
      (footprint "eagle-import:T_ROUND_3MM")
      (fields (field (name "PURPOSE") "RND5"))
      (libsource (lib "eagle-import") (part "LED_T_ROUND_3MM"))
    )
    (comp (ref "LED706")
      (value "LED_T_ROUND_3MM")
      (footprint "eagle-import:T_ROUND_3MM")
      (fields (field (name "PURPOSE") "RND6"))
      (libsource (lib "eagle-import") (part "LED_T_ROUND_3MM"))
    )
    (comp (ref "LED707")
      (value "LED_T_ROUND_3MM")
      (footprint "eagle-import:T_ROUND_3MM")
      (fields (field (name "PURPOSE") "RND7"))
      (libsource (lib "eagle-import") (part "LED_T_ROUND_3MM"))
    )
    (comp (ref "LED708")
      (value "LED_T_ROUND_3MM")
      (footprint "eagle-import:T_ROUND_3MM")
      (fields (field (name "PURPOSE") "RND8"))
      (libsource (lib "eagle-import") (part "LED_T_ROUND_3MM"))
    )
    (comp (ref "LED709")
      (value "LED_T_ROUND_3MM")
      (footprint "eagle-import:T_ROUND_3MM")
      (fields (field (name "PURPOSE") "RND9"))
      (libsource (lib "eagle-import") (part "LED_T_ROUND_3MM"))
    )
    (comp (ref "N701")
      (value "NET_CHANGER-S-0.3MM")
      (footprint "eagle-import:S_NET_CHANGER_0.3MM")
      (libsource (lib "eagle-import") (part "NET_CHANGER-S-0.3MM"))
    )
    (comp (ref "N702")
      (value "NET_CHANGER-S-0.3MM")
      (footprint "eagle-import:S_NET_CHANGER_0.3MM")
      (libsource (lib "eagle-import") (part "NET_CHANGER-S-0.3MM"))
    )
    (comp (ref "N703")
      (value "NET_CHANGER-S-0.3MM")
      (footprint "eagle-import:S_NET_CHANGER_0.3MM")
      (libsource (lib "eagle-import") (part "NET_CHANGER-S-0.3MM"))
    )
    (comp (ref "N704")
      (value "NET_CHANGER-S-0.3MM")
      (footprint "eagle-import:S_NET_CHANGER_0.3MM")
      (libsource (lib "eagle-import") (part "NET_CHANGER-S-0.3MM"))
    )
    (comp (ref "N705")
      (value "NET_CHANGER-S-0.3MM")
      (footprint "eagle-import:S_NET_CHANGER_0.3MM")
      (libsource (lib "eagle-import") (part "NET_CHANGER-S-0.3MM"))
    )
    (comp (ref "N706")
      (value "NET_CHANGER-S-0.3MM")
      (footprint "eagle-import:S_NET_CHANGER_0.3MM")
      (libsource (lib "eagle-import") (part "NET_CHANGER-S-0.3MM"))
    )
    (comp (ref "N707")
      (value "NET_CHANGER-S-0.3MM")
      (footprint "eagle-import:S_NET_CHANGER_0.3MM")
      (libsource (lib "eagle-import") (part "NET_CHANGER-S-0.3MM"))
    )
    (comp (ref "N708")
      (value "NET_CHANGER-S-0.3MM")
      (footprint "eagle-import:S_NET_CHANGER_0.3MM")
      (libsource (lib "eagle-import") (part "NET_CHANGER-S-0.3MM"))
    )
    (comp (ref "N709")
      (value "NET_CHANGER-S-0.3MM")
      (footprint "eagle-import:S_NET_CHANGER_0.3MM")
      (libsource (lib "eagle-import") (part "NET_CHANGER-S-0.3MM"))
    )
    (comp (ref "R701")
      (value "2k7")
      (footprint "eagle-import:T_0207_PITCH_10MM")
      (libsource (lib "eagle-import") (part "R_T_0207_PITCH_10MM"))
    )
    (comp (ref "R702")
      (value "2k7")
      (footprint "eagle-import:T_0207_PITCH_10MM")
      (libsource (lib "eagle-import") (part "R_T_0207_PITCH_10MM"))
    )
    (comp (ref "R703")
      (value "2k7")
      (footprint "eagle-import:T_0207_PITCH_10MM")
      (libsource (lib "eagle-import") (part "R_T_0207_PITCH_10MM"))
    )
    (comp (ref "R704")
      (value "330")
      (footprint "eagle-import:T_0207_PITCH_10MM")
      (fields (field (name "PART_CODE_BEL") "R_PAC_T_0207_PITCH_10mm_VAL_330"))
      (libsource (lib "eagle-import") (part "R_T_0207_PITCH_10MM"))
    )
    (comp (ref "R705")
      (value "330")
      (footprint "eagle-import:T_0207_PITCH_10MM")
      (fields (field (name "PART_CODE_BEL") "R_PAC_T_0207_PITCH_10mm_VAL_330"))
      (libsource (lib "eagle-import") (part "R_T_0207_PITCH_10MM"))
    )
    (comp (ref "R706")
      (value "330")
      (footprint "eagle-import:T_0207_PITCH_10MM")
      (fields (field (name "PART_CODE_BEL") "R_PAC_T_0207_PITCH_10mm_VAL_330"))
      (libsource (lib "eagle-import") (part "R_T_0207_PITCH_10MM"))
    )
    (comp (ref "R707")
      (value "2k7")
      (footprint "eagle-import:T_0207_PITCH_10MM")
      (libsource (lib "eagle-import") (part "R_T_0207_PITCH_10MM"))
    )
    (comp (ref "R708")
      (value "2k7")
      (footprint "eagle-import:T_0207_PITCH_10MM")
      (libsource (lib "eagle-import") (part "R_T_0207_PITCH_10MM"))
    )
    (comp (ref "R709")
      (value "2k7")
      (footprint "eagle-import:T_0207_PITCH_10MM")
      (libsource (lib "eagle-import") (part "R_T_0207_PITCH_10MM"))
    )
    (comp (ref "R710")
      (value "330")
      (footprint "eagle-import:T_0207_PITCH_10MM")
      (fields (field (name "PART_CODE_BEL") "R_PAC_T_0207_PITCH_10mm_VAL_330"))
      (libsource (lib "eagle-import") (part "R_T_0207_PITCH_10MM"))
    )
    (comp (ref "R711")
      (value "330")
      (footprint "eagle-import:T_0207_PITCH_10MM")
      (fields (field (name "PART_CODE_BEL") "R_PAC_T_0207_PITCH_10mm_VAL_330"))
      (libsource (lib "eagle-import") (part "R_T_0207_PITCH_10MM"))
    )
    (comp (ref "R712")
      (value "330")
      (footprint "eagle-import:T_0207_PITCH_10MM")
      (fields (field (name "PART_CODE_BEL") "R_PAC_T_0207_PITCH_10mm_VAL_330"))
      (libsource (lib "eagle-import") (part "R_T_0207_PITCH_10MM"))
    )
    (comp (ref "R713")
      (value "2k7")
      (footprint "eagle-import:T_0207_PITCH_10MM")
      (libsource (lib "eagle-import") (part "R_T_0207_PITCH_10MM"))
    )
    (comp (ref "R714")
      (value "2k7")
      (footprint "eagle-import:T_0207_PITCH_10MM")
      (libsource (lib "eagle-import") (part "R_T_0207_PITCH_10MM"))
    )
    (comp (ref "R715")
      (value "2k7")
      (footprint "eagle-import:T_0207_PITCH_10MM")
      (libsource (lib "eagle-import") (part "R_T_0207_PITCH_10MM"))
    )
    (comp (ref "R716")
      (value "330")
      (footprint "eagle-import:T_0207_PITCH_10MM")
      (fields (field (name "PART_CODE_BEL") "R_PAC_T_0207_PITCH_10mm_VAL_330"))
      (libsource (lib "eagle-import") (part "R_T_0207_PITCH_10MM"))
    )
    (comp (ref "R717")
      (value "330")
      (footprint "eagle-import:T_0207_PITCH_10MM")
      (fields (field (name "PART_CODE_BEL") "R_PAC_T_0207_PITCH_10mm_VAL_330"))
      (libsource (lib "eagle-import") (part "R_T_0207_PITCH_10MM"))
    )
    (comp (ref "R718")
      (value "330")
      (footprint "eagle-import:T_0207_PITCH_10MM")
      (fields (field (name "PART_CODE_BEL") "R_PAC_T_0207_PITCH_10mm_VAL_330"))
      (libsource (lib "eagle-import") (part "R_T_0207_PITCH_10MM"))
    )
    (comp (ref "T701")
      (value "BC548C")
      (footprint "eagle-import:T_TO92-CBE")
      (libsource (lib "eagle-import") (part "NPN_T_TO92-CBE"))
    )
    (comp (ref "T702")
      (value "BC548C")
      (footprint "eagle-import:T_TO92-CBE")
      (libsource (lib "eagle-import") (part "NPN_T_TO92-CBE"))
    )
    (comp (ref "T703")
      (value "BC548C")
      (footprint "eagle-import:T_TO92-CBE")
      (libsource (lib "eagle-import") (part "NPN_T_TO92-CBE"))
    )
    (comp (ref "T704")
      (value "BC548C")
      (footprint "eagle-import:T_TO92-CBE")
      (libsource (lib "eagle-import") (part "NPN_T_TO92-CBE"))
    )
    (comp (ref "T705")
      (value "BC548C")
      (footprint "eagle-import:T_TO92-CBE")
      (libsource (lib "eagle-import") (part "NPN_T_TO92-CBE"))
    )
    (comp (ref "T706")
      (value "BC548C")
      (footprint "eagle-import:T_TO92-CBE")
      (libsource (lib "eagle-import") (part "NPN_T_TO92-CBE"))
    )
    (comp (ref "T707")
      (value "BC548C")
      (footprint "eagle-import:T_TO92-CBE")
      (libsource (lib "eagle-import") (part "NPN_T_TO92-CBE"))
    )
    (comp (ref "T708")
      (value "BC548C")
      (footprint "eagle-import:T_TO92-CBE")
      (libsource (lib "eagle-import") (part "NPN_T_TO92-CBE"))
    )
    (comp (ref "T709")
      (value "BC548C")
      (footprint "eagle-import:T_TO92-CBE")
      (libsource (lib "eagle-import") (part "NPN_T_TO92-CBE"))
    )
    (comp (ref "H601")
      (value "HOLE_4.1_PAD")
      (footprint "eagle-import:4.1_PAD")
      (libsource (lib "eagle-import") (part "HOLE_4.1_PAD"))
    )
    (comp (ref "H602")
      (value "HOLE_4.1_PAD")
      (footprint "eagle-import:4.1_PAD")
      (libsource (lib "eagle-import") (part "HOLE_4.1_PAD"))
    )
    (comp (ref "H603")
      (value "HOLE_4.1_PAD")
      (footprint "eagle-import:4.1_PAD")
      (libsource (lib "eagle-import") (part "HOLE_4.1_PAD"))
    )
    (comp (ref "H604")
      (value "HOLE_4.1_PAD")
      (footprint "eagle-import:4.1_PAD")
      (libsource (lib "eagle-import") (part "HOLE_4.1_PAD"))
    )
    (comp (ref "RN601")
      (value "10k")
      (footprint "eagle-import:T_SIL8")
      (fields (field (name "PART_CODE_BEL") "RN_PAC_T_SIL8_VAL_10k"))
      (libsource (lib "eagle-import") (part "RN_4T_SIL8"))
    )
    (comp (ref "TP601")
      (value "TEST_POINT_T_SMALL")
      (footprint "eagle-import:T_TEST_POINT_SMALL")
      (libsource (lib "eagle-import") (part "TEST_POINT_T_SMALL"))
    )
    (comp (ref "TP602")
      (value "TEST_POINT_T_SMALL")
      (footprint "eagle-import:T_TEST_POINT_SMALL")
      (libsource (lib "eagle-import") (part "TEST_POINT_T_SMALL"))
    )
    (comp (ref "TP603")
      (value "TEST_POINT_T_SMALL")
      (footprint "eagle-import:T_TEST_POINT_SMALL")
      (libsource (lib "eagle-import") (part "TEST_POINT_T_SMALL"))
    )
    (comp (ref "TP604")
      (value "TEST_POINT_T_SMALL")
      (footprint "eagle-import:T_TEST_POINT_SMALL")
      (libsource (lib "eagle-import") (part "TEST_POINT_T_SMALL"))
    )
    (comp (ref "TP605")
      (value "TEST_POINT_T_SMALL")
      (footprint "eagle-import:T_TEST_POINT_SMALL")
      (libsource (lib "eagle-import") (part "TEST_POINT_T_SMALL"))
    )
    (comp (ref "TP606")
      (value "TEST_POINT_T_SMALL")
      (footprint "eagle-import:T_TEST_POINT_SMALL")
      (libsource (lib "eagle-import") (part "TEST_POINT_T_SMALL"))
    )
    (comp (ref "LED801")
      (value "LED_T_ROUND_3MM")
      (footprint "eagle-import:T_ROUND_3MM")
      (fields (field (name "PURPOSE") "RND10"))
      (libsource (lib "eagle-import") (part "LED_T_ROUND_3MM"))
    )
    (comp (ref "LED802")
      (value "LED_T_ROUND_3MM")
      (footprint "eagle-import:T_ROUND_3MM")
      (fields (field (name "PURPOSE") "RND11"))
      (libsource (lib "eagle-import") (part "LED_T_ROUND_3MM"))
    )
    (comp (ref "LED803")
      (value "LED_T_ROUND_3MM")
      (footprint "eagle-import:T_ROUND_3MM")
      (fields (field (name "PURPOSE") "RND12"))
      (libsource (lib "eagle-import") (part "LED_T_ROUND_3MM"))
    )
    (comp (ref "LED804")
      (value "LED_T_ROUND_3MM")
      (footprint "eagle-import:T_ROUND_3MM")
      (fields (field (name "PURPOSE") "RND13"))
      (libsource (lib "eagle-import") (part "LED_T_ROUND_3MM"))
    )
    (comp (ref "LED805")
      (value "LED_T_ROUND_3MM")
      (footprint "eagle-import:T_ROUND_3MM")
      (fields (field (name "PURPOSE") "RND14"))
      (libsource (lib "eagle-import") (part "LED_T_ROUND_3MM"))
    )
    (comp (ref "LED806")
      (value "LED_T_ROUND_3MM")
      (footprint "eagle-import:T_ROUND_3MM")
      (fields (field (name "PURPOSE") "RND15"))
      (libsource (lib "eagle-import") (part "LED_T_ROUND_3MM"))
    )
    (comp (ref "LED807")
      (value "LED_T_ROUND_3MM")
      (footprint "eagle-import:T_ROUND_3MM")
      (fields (field (name "PURPOSE") "RND16"))
      (libsource (lib "eagle-import") (part "LED_T_ROUND_3MM"))
    )
    (comp (ref "N801")
      (value "NET_CHANGER-S-0.3MM")
      (footprint "eagle-import:S_NET_CHANGER_0.3MM")
      (libsource (lib "eagle-import") (part "NET_CHANGER-S-0.3MM"))
    )
    (comp (ref "N802")
      (value "NET_CHANGER-S-0.3MM")
      (footprint "eagle-import:S_NET_CHANGER_0.3MM")
      (libsource (lib "eagle-import") (part "NET_CHANGER-S-0.3MM"))
    )
    (comp (ref "N803")
      (value "NET_CHANGER-S-0.3MM")
      (footprint "eagle-import:S_NET_CHANGER_0.3MM")
      (libsource (lib "eagle-import") (part "NET_CHANGER-S-0.3MM"))
    )
    (comp (ref "N804")
      (value "NET_CHANGER-S-0.3MM")
      (footprint "eagle-import:S_NET_CHANGER_0.3MM")
      (libsource (lib "eagle-import") (part "NET_CHANGER-S-0.3MM"))
    )
    (comp (ref "N805")
      (value "NET_CHANGER-S-0.3MM")
      (footprint "eagle-import:S_NET_CHANGER_0.3MM")
      (libsource (lib "eagle-import") (part "NET_CHANGER-S-0.3MM"))
    )
    (comp (ref "N806")
      (value "NET_CHANGER-S-0.3MM")
      (footprint "eagle-import:S_NET_CHANGER_0.3MM")
      (libsource (lib "eagle-import") (part "NET_CHANGER-S-0.3MM"))
    )
    (comp (ref "N807")
      (value "NET_CHANGER-S-0.3MM")
      (footprint "eagle-import:S_NET_CHANGER_0.3MM")
      (libsource (lib "eagle-import") (part "NET_CHANGER-S-0.3MM"))
    )
    (comp (ref "R801")
      (value "2k7")
      (footprint "eagle-import:T_0207_PITCH_10MM")
      (libsource (lib "eagle-import") (part "R_T_0207_PITCH_10MM"))
    )
    (comp (ref "R802")
      (value "2k7")
      (footprint "eagle-import:T_0207_PITCH_10MM")
      (libsource (lib "eagle-import") (part "R_T_0207_PITCH_10MM"))
    )
    (comp (ref "R803")
      (value "2k7")
      (footprint "eagle-import:T_0207_PITCH_10MM")
      (libsource (lib "eagle-import") (part "R_T_0207_PITCH_10MM"))
    )
    (comp (ref "R804")
      (value "330")
      (footprint "eagle-import:T_0207_PITCH_10MM")
      (fields (field (name "PART_CODE_BEL") "R_PAC_T_0207_PITCH_10mm_VAL_330"))
      (libsource (lib "eagle-import") (part "R_T_0207_PITCH_10MM"))
    )
    (comp (ref "R805")
      (value "330")
      (footprint "eagle-import:T_0207_PITCH_10MM")
      (fields (field (name "PART_CODE_BEL") "R_PAC_T_0207_PITCH_10mm_VAL_330"))
      (libsource (lib "eagle-import") (part "R_T_0207_PITCH_10MM"))
    )
    (comp (ref "R806")
      (value "330")
      (footprint "eagle-import:T_0207_PITCH_10MM")
      (fields (field (name "PART_CODE_BEL") "R_PAC_T_0207_PITCH_10mm_VAL_330"))
      (libsource (lib "eagle-import") (part "R_T_0207_PITCH_10MM"))
    )
    (comp (ref "R807")
      (value "2k7")
      (footprint "eagle-import:T_0207_PITCH_10MM")
      (libsource (lib "eagle-import") (part "R_T_0207_PITCH_10MM"))
    )
    (comp (ref "R808")
      (value "2k7")
      (footprint "eagle-import:T_0207_PITCH_10MM")
      (libsource (lib "eagle-import") (part "R_T_0207_PITCH_10MM"))
    )
    (comp (ref "R809")
      (value "2k7")
      (footprint "eagle-import:T_0207_PITCH_10MM")
      (libsource (lib "eagle-import") (part "R_T_0207_PITCH_10MM"))
    )
    (comp (ref "R810")
      (value "330")
      (footprint "eagle-import:T_0207_PITCH_10MM")
      (fields (field (name "PART_CODE_BEL") "R_PAC_T_0207_PITCH_10mm_VAL_330"))
      (libsource (lib "eagle-import") (part "R_T_0207_PITCH_10MM"))
    )
    (comp (ref "R811")
      (value "330")
      (footprint "eagle-import:T_0207_PITCH_10MM")
      (fields (field (name "PART_CODE_BEL") "R_PAC_T_0207_PITCH_10mm_VAL_330"))
      (libsource (lib "eagle-import") (part "R_T_0207_PITCH_10MM"))
    )
    (comp (ref "R812")
      (value "330")
      (footprint "eagle-import:T_0207_PITCH_10MM")
      (fields (field (name "PART_CODE_BEL") "R_PAC_T_0207_PITCH_10mm_VAL_330"))
      (libsource (lib "eagle-import") (part "R_T_0207_PITCH_10MM"))
    )
    (comp (ref "R813")
      (value "2k7")
      (footprint "eagle-import:T_0207_PITCH_10MM")
      (libsource (lib "eagle-import") (part "R_T_0207_PITCH_10MM"))
    )
    (comp (ref "R814")
      (value "330")
      (footprint "eagle-import:T_0207_PITCH_10MM")
      (fields (field (name "PART_CODE_BEL") "R_PAC_T_0207_PITCH_10mm_VAL_330"))
      (libsource (lib "eagle-import") (part "R_T_0207_PITCH_10MM"))
    )
    (comp (ref "T801")
      (value "BC548C")
      (footprint "eagle-import:T_TO92-CBE")
      (libsource (lib "eagle-import") (part "NPN_T_TO92-CBE"))
    )
    (comp (ref "T802")
      (value "BC548C")
      (footprint "eagle-import:T_TO92-CBE")
      (libsource (lib "eagle-import") (part "NPN_T_TO92-CBE"))
    )
    (comp (ref "T803")
      (value "BC548C")
      (footprint "eagle-import:T_TO92-CBE")
      (libsource (lib "eagle-import") (part "NPN_T_TO92-CBE"))
    )
    (comp (ref "T804")
      (value "BC548C")
      (footprint "eagle-import:T_TO92-CBE")
      (libsource (lib "eagle-import") (part "NPN_T_TO92-CBE"))
    )
    (comp (ref "T805")
      (value "BC548C")
      (footprint "eagle-import:T_TO92-CBE")
      (libsource (lib "eagle-import") (part "NPN_T_TO92-CBE"))
    )
    (comp (ref "T806")
      (value "BC548C")
      (footprint "eagle-import:T_TO92-CBE")
      (libsource (lib "eagle-import") (part "NPN_T_TO92-CBE"))
    )
    (comp (ref "T807")
      (value "BC548C")
      (footprint "eagle-import:T_TO92-CBE")
      (libsource (lib "eagle-import") (part "NPN_T_TO92-CBE"))
    )
    (comp (ref "C201")
      (value "100n")
      (footprint "eagle-import:T_DISC_4MM_PITCH_5MM")
      (fields (field (name "PART_CODE_BEL") "C_PAC_T_DISC_7mm_PITCH_5mm_VAL_100n"))
      (libsource (lib "eagle-import") (part "C_T_DISC_4MM_PITCH_5MM"))
    )
    (comp (ref "C202")
      (value "100n")
      (footprint "eagle-import:T_DISC_4MM_PITCH_5MM")
      (fields (field (name "PART_CODE_BEL") "C_PAC_T_DISC_7mm_PITCH_5mm_VAL_100n"))
      (libsource (lib "eagle-import") (part "C_T_DISC_4MM_PITCH_5MM"))
    )
    (comp (ref "IC201")
      (value "7495N")
      (footprint "eagle-import:T_NDIP14")
      (fields (field (name "PART_CODE_BEL") "IC_PAC_T_NDIP14_VAL_SN7495N"))
      (libsource (lib "eagle-import") (part "7495N"))
    )
    (comp (ref "IC202")
      (value "74175N")
      (footprint "eagle-import:T_NDIP16")
      (fields (field (name "PART_CODE_BEL") "IC_PAC_NDIP16_VAL_SN74175N"))
      (libsource (lib "eagle-import") (part "74175N"))
    )
    (comp (ref "N201")
      (value "NET_CHANGER-S-0.3MM")
      (footprint "eagle-import:S_NET_CHANGER_0.3MM")
      (libsource (lib "eagle-import") (part "NET_CHANGER-S-0.3MM"))
    )
    (comp (ref "TP201")
      (value "TEST_POINT_T_SMALL")
      (footprint "eagle-import:T_TEST_POINT_SMALL")
      (libsource (lib "eagle-import") (part "TEST_POINT_T_SMALL"))
    )
    (comp (ref "X1101")
      (value "MALE_2X13-T-VERTICAL_PITCH_2MM54")
      (footprint "eagle-import:T_MALE_2X13_VERTICAL_PITCH_2MM54")
      (fields (field (name "FUNCTION") "RANDOM DATA OUT"))
      (libsource (lib "eagle-import") (part "MALE_2X13-T-VERTICAL_PITCH_2MM54"))
    )
    (comp (ref "C401")
      (value "100n")
      (footprint "eagle-import:T_DISC_4MM_PITCH_5MM")
      (fields (field (name "PART_CODE_BEL") "C_PAC_T_DISC_7mm_PITCH_5mm_VAL_100n"))
      (libsource (lib "eagle-import") (part "C_T_DISC_4MM_PITCH_5MM"))
    )
    (comp (ref "C402")
      (value "100n")
      (footprint "eagle-import:T_DISC_4MM_PITCH_5MM")
      (fields (field (name "PART_CODE_BEL") "C_PAC_T_DISC_7mm_PITCH_5mm_VAL_100n"))
      (libsource (lib "eagle-import") (part "C_T_DISC_4MM_PITCH_5MM"))
    )
    (comp (ref "IC401")
      (value "7495N")
      (footprint "eagle-import:T_NDIP14")
      (fields (field (name "PART_CODE_BEL") "IC_PAC_T_NDIP14_VAL_SN7495N"))
      (libsource (lib "eagle-import") (part "7495N"))
    )
    (comp (ref "IC402")
      (value "74175N")
      (footprint "eagle-import:T_NDIP16")
      (fields (field (name "PART_CODE_BEL") "IC_PAC_NDIP16_VAL_SN74175N"))
      (libsource (lib "eagle-import") (part "74175N"))
    )
    (comp (ref "N401")
      (value "NET_CHANGER-S-0.3MM")
      (footprint "eagle-import:S_NET_CHANGER_0.3MM")
      (libsource (lib "eagle-import") (part "NET_CHANGER-S-0.3MM"))
    )
    (comp (ref "TP401")
      (value "TEST_POINT_T_SMALL")
      (footprint "eagle-import:T_TEST_POINT_SMALL")
      (libsource (lib "eagle-import") (part "TEST_POINT_T_SMALL"))
    )
    (comp (ref "C901")
      (value "100n")
      (footprint "eagle-import:T_DISC_4MM_PITCH_5MM")
      (fields (field (name "PART_CODE_BEL") "C_PAC_S_0805_VAL_100n"))
      (libsource (lib "eagle-import") (part "C_T_DISC_4MM_PITCH_5MM"))
    )
    (comp (ref "C902")
      (value "47n")
      (footprint "eagle-import:T_DISC_4MM_PITCH_5MM")
      (fields (field (name "PART_CODE_BEL") "C_PAC_S_0805_VAL_47n"))
      (libsource (lib "eagle-import") (part "C_T_DISC_4MM_PITCH_5MM"))
    )
    (comp (ref "C903")
      (value "10n")
      (footprint "eagle-import:T_DISC_4MM_PITCH_5MM")
      (fields (field (name "PART_CODE_BEL") "C_PAC_S_0805_VAL_10n"))
      (libsource (lib "eagle-import") (part "C_T_DISC_4MM_PITCH_5MM"))
    )
    (comp (ref "D901")
      (value "SAY32")
      (footprint "eagle-import:T_MINIPLAST")
      (libsource (lib "eagle-import") (part "SINGLE_T_MINIPLAST"))
    )
    (comp (ref "IC901")
      (value "NE555V")
      (footprint "eagle-import:T_NDIP8")
      (fields (field (name "PART_CODE_BEL") "IC_PAC_T_NDIP8_VAL_NE555V"))
      (libsource (lib "eagle-import") (part "555P"))
    )
    (comp (ref "R901")
      (value "1k2")
      (footprint "eagle-import:T_0207_PITCH_10MM")
      (fields (field (name "PART_CODE_BEL") "R_PAC_S_0805_VAL_10k"))
      (libsource (lib "eagle-import") (part "R_T_0207_PITCH_10MM"))
    )
    (comp (ref "R902")
      (value "not fitted")
      (footprint "eagle-import:T_0207_PITCH_10MM")
      (fields (field (name "PART_CODE_BEL") "R_PAC_S_0805_VAL_470k"))
      (libsource (lib "eagle-import") (part "R_T_0207_PITCH_10MM"))
    )
    (comp (ref "R903")
      (value "1k")
      (footprint "eagle-import:T_0207_PITCH_10MM")
      (fields (field (name "PART_CODE_BEL") "R_PAC_S_0805_VAL_1k"))
      (libsource (lib "eagle-import") (part "R_T_0207_PITCH_10MM"))
    )
    (comp (ref "R904")
      (value "1M")
      (footprint "eagle-import:T_TRIM_PIHER_PT10_HORIZONTAL")
      (fields (field (name "FUNCTION") "BRIGHTNESS"))
      (libsource (lib "eagle-import") (part "RA_T_PT10_HORIZONTAL"))
    )
    (comp (ref "R905")
      (value "10k")
      (footprint "eagle-import:T_0207_PITCH_10MM")
      (fields (field (name "PART_CODE_BEL") "R_PAC_S_0805_VAL_10k"))
      (libsource (lib "eagle-import") (part "R_T_0207_PITCH_10MM"))
    )
    (comp (ref "R906")
      (value "330")
      (footprint "eagle-import:T_0207_PITCH_10MM")
      (fields (field (name "PART_CODE_BEL") "R_PAC_S_0805_VAL_330"))
      (libsource (lib "eagle-import") (part "R_T_0207_PITCH_10MM"))
    )
    (comp (ref "RPH901")
      (value "RPH")
      (footprint "eagle-import:T_TO39-2")
      (fields (field (name "FUNCTION") "LIGHT SENSOR"))
      (libsource (lib "eagle-import") (part "RPH"))
    )
    (comp (ref "T901")
      (value "BD136")
      (footprint "eagle-import:T_TO126_VERTICAL")
      (libsource (lib "eagle-import") (part "PNP_T_TO126_VERTICAL"))
    )
    (comp (ref "C501")
      (value "100n")
      (footprint "eagle-import:T_DISC_4MM_PITCH_5MM")
      (fields (field (name "PART_CODE_BEL") "C_PAC_T_DISC_7mm_PITCH_5mm_VAL_100n"))
      (libsource (lib "eagle-import") (part "C_T_DISC_4MM_PITCH_5MM"))
    )
    (comp (ref "C502")
      (value "100n")
      (footprint "eagle-import:T_DISC_4MM_PITCH_5MM")
      (fields (field (name "PART_CODE_BEL") "C_PAC_T_DISC_7mm_PITCH_5mm_VAL_100n"))
      (libsource (lib "eagle-import") (part "C_T_DISC_4MM_PITCH_5MM"))
    )
    (comp (ref "IC501")
      (value "7495N")
      (footprint "eagle-import:T_NDIP14")
      (fields (field (name "PART_CODE_BEL") "IC_PAC_T_NDIP14_VAL_SN7495N"))
      (libsource (lib "eagle-import") (part "7495N"))
    )
    (comp (ref "IC502")
      (value "74175N")
      (footprint "eagle-import:T_NDIP16")
      (fields (field (name "PART_CODE_BEL") "IC_PAC_NDIP16_VAL_SN74175N"))
      (libsource (lib "eagle-import") (part "74175N"))
    )
    (comp (ref "N501")
      (value "NET_CHANGER-S-0.3MM")
      (footprint "eagle-import:S_NET_CHANGER_0.3MM")
      (libsource (lib "eagle-import") (part "NET_CHANGER-S-0.3MM"))
    )
    (comp (ref "TP501")
      (value "TEST_POINT_T_SMALL")
      (footprint "eagle-import:T_TEST_POINT_SMALL")
      (libsource (lib "eagle-import") (part "TEST_POINT_T_SMALL"))
    )
    (comp (ref "C1001")
      (value "470u")
      (footprint "eagle-import:T_RADIAL_16MM_GRID_7.5MM")
      (libsource (lib "eagle-import") (part "C_POL_T_RAD16_GRID_7.5"))
    )
    (comp (ref "C1002")
      (value "330n")
      (footprint "eagle-import:T_DISC_7MM_PITCH_5MM")
      (libsource (lib "eagle-import") (part "C_T_DSIC_7MM_PITCH_5MM"))
    )
    (comp (ref "C1003")
      (value "100n")
      (footprint "eagle-import:T_DISC_4MM_PITCH_5MM")
      (libsource (lib "eagle-import") (part "C_T_DISC_4MM_PITCH_5MM"))
    )
    (comp (ref "D1001")
      (value "1N4001")
      (footprint "eagle-import:T_DO201_GRID_18MM")
      (libsource (lib "eagle-import") (part "SINGLE_T_DO201_GRID_18MM"))
    )
    (comp (ref "D1002")
      (value "1N4001")
      (footprint "eagle-import:T_DO201_GRID_18MM")
      (libsource (lib "eagle-import") (part "SINGLE_T_DO201_GRID_18MM"))
    )
    (comp (ref "D1003")
      (value "1N4001")
      (footprint "eagle-import:T_DO201_GRID_18MM")
      (libsource (lib "eagle-import") (part "SINGLE_T_DO201_GRID_18MM"))
    )
    (comp (ref "D1004")
      (value "1N4001")
      (footprint "eagle-import:T_DO201_GRID_18MM")
      (libsource (lib "eagle-import") (part "SINGLE_T_DO201_GRID_18MM"))
    )
    (comp (ref "IC1001")
      (value "7805_T_HORIZONTAL")
      (footprint "eagle-import:T_TO220-3_HORIZONTAL")
      (libsource (lib "eagle-import") (part "78XX_T_HORIZONTAL"))
    )
    (comp (ref "J1001")
      (value "SOLDER_JUMPER-N")
      (footprint "eagle-import:S_SOLDER_JUMPER_NARROW")
      (libsource (lib "eagle-import") (part "SOLDER_JUMPER-N"))
    )
    (comp (ref "LED1001")
      (value "green")
      (footprint "eagle-import:T_ROUND_3MM")
      (fields
        (field (name "FUNCTION") "PWR_ON")
        (field (name "PART_CODE_BEL") "LED_PAC_T_ROUND_3mm_VAL_green")
      )
      (libsource (lib "eagle-import") (part "LED_T_ROUND_3MM"))
    )
    (comp (ref "R1001")
      (value "330")
      (footprint "eagle-import:T_0207_PITCH_10MM")
      (fields (field (name "PART_CODE_BEL") "R_PAC_T_0207_PITCH_10mm_VAL_330"))
      (libsource (lib "eagle-import") (part "R_T_0207_PITCH_10MM"))
    )
    (comp (ref "X1001")
      (value "CLAMP_1X2-T-5MM")
      (footprint "eagle-import:T_WIRE_CLAMP_1X2_PITCH_5MM")
      (fields (field (name "FUNCTION") "PWR_IN"))
      (libsource (lib "eagle-import") (part "CLAMP_1X2-T-5MM"))
    )
  )
  (nets
    (net (code "1") (name "CLK_FAST") (class "Default")
      (node (ref "IC102") (pin "6") (pinfunction "O_6") (pintype "output"))
      (node (ref "N201") (pin "1") (pinfunction "1_1") (pintype "passive"))
    )
    (net (code "2") (name "CLK_SLOW") (class "Default")
      (node (ref "IC102") (pin "8") (pinfunction "O_8") (pintype "output"))
      (node (ref "IC103") (pin "5") (pinfunction "UP_5") (pintype "input"))
      (node (ref "TP104") (pin "1") (pinfunction "TP_1") (pintype "passive"))
    )
    (net (code "3") (name "CLK_SLOW_N") (class "Default")
      (node (ref "IC102") (pin "10") (pinfunction "I0_10") (pintype "input"))
      (node (ref "IC102") (pin "3") (pinfunction "O_3") (pintype "output"))
      (node (ref "IC201") (pin "9") (pinfunction "C1_9") (pintype "input"))
      (node (ref "IC301") (pin "9") (pinfunction "C1_9") (pintype "input"))
      (node (ref "IC401") (pin "9") (pinfunction "C1_9") (pintype "input"))
      (node (ref "IC501") (pin "9") (pinfunction "C1_9") (pintype "input"))
      (node (ref "TP103") (pin "1") (pinfunction "TP_1") (pintype "passive"))
    )
    (net (code "4") (name "CLK_SLOW_OSC") (class "Default")
      (node (ref "IC101") (pin "4") (pinfunction "O_4") (pintype "output"))
      (node (ref "IC102") (pin "1") (pinfunction "I0_1") (pintype "input"))
      (node (ref "R103") (pin "B") (pinfunction "B_B") (pintype "passive"))
      (node (ref "TP102") (pin "1") (pinfunction "TP_1") (pintype "passive"))
    )
    (net (code "5") (name "DRV_OUT_1") (class "Default")
      (node (ref "LED701") (pin "C") (pinfunction "C_C") (pintype "passive"))
      (node (ref "T701") (pin "C") (pinfunction "C_C") (pintype "passive"))
      (node (ref "X1101") (pin "1") (pinfunction "1_1") (pintype "passive"))
    )
    (net (code "6") (name "DRV_OUT_2") (class "Default")
      (node (ref "LED702") (pin "C") (pinfunction "C_C") (pintype "passive"))
      (node (ref "T702") (pin "C") (pinfunction "C_C") (pintype "passive"))
      (node (ref "X1101") (pin "3") (pinfunction "3_3") (pintype "passive"))
    )
    (net (code "7") (name "DRV_OUT_3") (class "Default")
      (node (ref "LED703") (pin "C") (pinfunction "C_C") (pintype "passive"))
      (node (ref "T703") (pin "C") (pinfunction "C_C") (pintype "passive"))
      (node (ref "X1101") (pin "5") (pinfunction "5_5") (pintype "passive"))
    )
    (net (code "8") (name "DRV_OUT_4") (class "Default")
      (node (ref "LED704") (pin "C") (pinfunction "C_C") (pintype "passive"))
      (node (ref "T704") (pin "C") (pinfunction "C_C") (pintype "passive"))
      (node (ref "X1101") (pin "7") (pinfunction "7_7") (pintype "passive"))
    )
    (net (code "9") (name "DRV_OUT_5") (class "Default")
      (node (ref "LED705") (pin "C") (pinfunction "C_C") (pintype "passive"))
      (node (ref "T705") (pin "C") (pinfunction "C_C") (pintype "passive"))
      (node (ref "X1101") (pin "9") (pinfunction "9_9") (pintype "passive"))
    )
    (net (code "10") (name "DRV_OUT_6") (class "Default")
      (node (ref "LED706") (pin "C") (pinfunction "C_C") (pintype "passive"))
      (node (ref "T706") (pin "C") (pinfunction "C_C") (pintype "passive"))
      (node (ref "X1101") (pin "11") (pinfunction "11_11") (pintype "passive"))
    )
    (net (code "11") (name "DRV_OUT_7") (class "Default")
      (node (ref "LED707") (pin "C") (pinfunction "C_C") (pintype "passive"))
      (node (ref "T707") (pin "C") (pinfunction "C_C") (pintype "passive"))
      (node (ref "X1101") (pin "13") (pinfunction "13_13") (pintype "passive"))
    )
    (net (code "12") (name "DRV_OUT_8") (class "Default")
      (node (ref "LED708") (pin "C") (pinfunction "C_C") (pintype "passive"))
      (node (ref "T708") (pin "C") (pinfunction "C_C") (pintype "passive"))
      (node (ref "X1101") (pin "15") (pinfunction "15_15") (pintype "passive"))
    )
    (net (code "13") (name "DRV_OUT_9") (class "Default")
      (node (ref "LED709") (pin "C") (pinfunction "C_C") (pintype "passive"))
      (node (ref "T709") (pin "C") (pinfunction "C_C") (pintype "passive"))
      (node (ref "X1101") (pin "17") (pinfunction "17_17") (pintype "passive"))
    )
    (net (code "14") (name "DRV_OUT_10") (class "Default")
      (node (ref "LED801") (pin "C") (pinfunction "C_C") (pintype "passive"))
      (node (ref "T801") (pin "C") (pinfunction "C_C") (pintype "passive"))
      (node (ref "X1101") (pin "19") (pinfunction "19_19") (pintype "passive"))
    )
    (net (code "15") (name "DRV_OUT_11") (class "Default")
      (node (ref "LED802") (pin "C") (pinfunction "C_C") (pintype "passive"))
      (node (ref "T802") (pin "C") (pinfunction "C_C") (pintype "passive"))
      (node (ref "X1101") (pin "21") (pinfunction "21_21") (pintype "passive"))
    )
    (net (code "16") (name "DRV_OUT_12") (class "Default")
      (node (ref "LED803") (pin "C") (pinfunction "C_C") (pintype "passive"))
      (node (ref "T803") (pin "C") (pinfunction "C_C") (pintype "passive"))
      (node (ref "X1101") (pin "23") (pinfunction "23_23") (pintype "passive"))
    )
    (net (code "17") (name "DRV_OUT_13") (class "Default")
      (node (ref "LED804") (pin "C") (pinfunction "C_C") (pintype "passive"))
      (node (ref "T804") (pin "C") (pinfunction "C_C") (pintype "passive"))
      (node (ref "X1101") (pin "25") (pinfunction "25_25") (pintype "passive"))
    )
    (net (code "18") (name "DRV_OUT_14") (class "Default")
      (node (ref "LED805") (pin "C") (pinfunction "C_C") (pintype "passive"))
      (node (ref "T805") (pin "C") (pinfunction "C_C") (pintype "passive"))
      (node (ref "X1101") (pin "2") (pinfunction "2_2") (pintype "passive"))
    )
    (net (code "19") (name "DRV_OUT_15") (class "Default")
      (node (ref "LED806") (pin "C") (pinfunction "C_C") (pintype "passive"))
      (node (ref "T806") (pin "C") (pinfunction "C_C") (pintype "passive"))
      (node (ref "X1101") (pin "4") (pinfunction "4_4") (pintype "passive"))
    )
    (net (code "20") (name "DRV_OUT_16") (class "Default")
      (node (ref "LED807") (pin "C") (pinfunction "C_C") (pintype "passive"))
      (node (ref "T807") (pin "C") (pinfunction "C_C") (pintype "passive"))
      (node (ref "X1101") (pin "6") (pinfunction "6_6") (pintype "passive"))
    )
    (net (code "21") (name "GND") (class "Default")
      (node (ref "C1001") (pin "-") (pinfunction "-_-") (pintype "passive"))
      (node (ref "C1002") (pin "2") (pinfunction "2_2") (pintype "passive"))
      (node (ref "C1003") (pin "2") (pinfunction "2_2") (pintype "passive"))
      (node (ref "C101") (pin "-") (pinfunction "-_-") (pintype "passive"))
      (node (ref "C102") (pin "2") (pinfunction "2_2") (pintype "passive"))
      (node (ref "C103") (pin "2") (pinfunction "2_2") (pintype "passive"))
      (node (ref "C104") (pin "2") (pinfunction "2_2") (pintype "passive"))
      (node (ref "C105") (pin "2") (pinfunction "2_2") (pintype "passive"))
      (node (ref "C201") (pin "2") (pinfunction "2_2") (pintype "passive"))
      (node (ref "C202") (pin "2") (pinfunction "2_2") (pintype "passive"))
      (node (ref "C301") (pin "2") (pinfunction "2_2") (pintype "passive"))
      (node (ref "C302") (pin "2") (pinfunction "2_2") (pintype "passive"))
      (node (ref "C401") (pin "2") (pinfunction "2_2") (pintype "passive"))
      (node (ref "C402") (pin "2") (pinfunction "2_2") (pintype "passive"))
      (node (ref "C501") (pin "2") (pinfunction "2_2") (pintype "passive"))
      (node (ref "C502") (pin "2") (pinfunction "2_2") (pintype "passive"))
      (node (ref "C901") (pin "2") (pinfunction "2_2") (pintype "passive"))
      (node (ref "C902") (pin "2") (pinfunction "2_2") (pintype "passive"))
      (node (ref "C903") (pin "2") (pinfunction "2_2") (pintype "passive"))
      (node (ref "D1003") (pin "A") (pinfunction "A_A") (pintype "passive"))
      (node (ref "D1004") (pin "A") (pinfunction "A_A") (pintype "passive"))
      (node (ref "IC1001") (pin "2") (pinfunction "GND_2") (pintype "power_in"))
      (node (ref "IC101") (pin "7") (pinfunction "GND_7") (pintype "power_in"))
      (node (ref "IC102") (pin "7") (pinfunction "GND_7") (pintype "power_in"))
      (node (ref "IC103") (pin "1") (pinfunction "DB_1") (pintype "input"))
      (node (ref "IC103") (pin "10") (pinfunction "DC_10") (pintype "input"))
      (node (ref "IC103") (pin "14") (pinfunction "CLR_14") (pintype "input"))
      (node (ref "IC103") (pin "15") (pinfunction "DA_15") (pintype "input"))
      (node (ref "IC103") (pin "8") (pinfunction "GND_8") (pintype "power_in"))
      (node (ref "IC103") (pin "9") (pinfunction "DD_9") (pintype "input"))
      (node (ref "IC201") (pin "2") (pinfunction "DA_2") (pintype "input"))
      (node (ref "IC201") (pin "3") (pinfunction "DB_3") (pintype "input"))
      (node (ref "IC201") (pin "4") (pinfunction "DC_4") (pintype "input"))
      (node (ref "IC201") (pin "5") (pinfunction "DD_5") (pintype "input"))
      (node (ref "IC201") (pin "6") (pinfunction "MC_6") (pintype "input"))
      (node (ref "IC201") (pin "7") (pinfunction "GND_7") (pintype "power_in"))
      (node (ref "IC201") (pin "8") (pinfunction "C2_8") (pintype "input"))
      (node (ref "IC202") (pin "8") (pinfunction "GND_8") (pintype "power_in"))
      (node (ref "IC301") (pin "2") (pinfunction "DA_2") (pintype "input"))
      (node (ref "IC301") (pin "3") (pinfunction "DB_3") (pintype "input"))
      (node (ref "IC301") (pin "4") (pinfunction "DC_4") (pintype "input"))
      (node (ref "IC301") (pin "5") (pinfunction "DD_5") (pintype "input"))
      (node (ref "IC301") (pin "6") (pinfunction "MC_6") (pintype "input"))
      (node (ref "IC301") (pin "7") (pinfunction "GND_7") (pintype "power_in"))
      (node (ref "IC301") (pin "8") (pinfunction "C2_8") (pintype "input"))
      (node (ref "IC302") (pin "8") (pinfunction "GND_8") (pintype "power_in"))
      (node (ref "IC401") (pin "2") (pinfunction "DA_2") (pintype "input"))
      (node (ref "IC401") (pin "3") (pinfunction "DB_3") (pintype "input"))
      (node (ref "IC401") (pin "4") (pinfunction "DC_4") (pintype "input"))
      (node (ref "IC401") (pin "5") (pinfunction "DD_5") (pintype "input"))
      (node (ref "IC401") (pin "6") (pinfunction "MC_6") (pintype "input"))
      (node (ref "IC401") (pin "7") (pinfunction "GND_7") (pintype "power_in"))
      (node (ref "IC401") (pin "8") (pinfunction "C2_8") (pintype "input"))
      (node (ref "IC402") (pin "8") (pinfunction "GND_8") (pintype "power_in"))
      (node (ref "IC501") (pin "2") (pinfunction "DA_2") (pintype "input"))
      (node (ref "IC501") (pin "3") (pinfunction "DB_3") (pintype "input"))
      (node (ref "IC501") (pin "4") (pinfunction "DC_4") (pintype "input"))
      (node (ref "IC501") (pin "5") (pinfunction "DD_5") (pintype "input"))
      (node (ref "IC501") (pin "6") (pinfunction "MC_6") (pintype "input"))
      (node (ref "IC501") (pin "7") (pinfunction "GND_7") (pintype "power_in"))
      (node (ref "IC501") (pin "8") (pinfunction "C2_8") (pintype "input"))
      (node (ref "IC502") (pin "8") (pinfunction "GND_8") (pintype "power_in"))
      (node (ref "IC901") (pin "1") (pinfunction "GND_1") (pintype "power_in"))
      (node (ref "LED1001") (pin "C") (pinfunction "C_C") (pintype "passive"))
      (node (ref "T701") (pin "E") (pinfunction "E_E") (pintype "passive"))
      (node (ref "T702") (pin "E") (pinfunction "E_E") (pintype "passive"))
      (node (ref "T703") (pin "E") (pinfunction "E_E") (pintype "passive"))
      (node (ref "T704") (pin "E") (pinfunction "E_E") (pintype "passive"))
      (node (ref "T705") (pin "E") (pinfunction "E_E") (pintype "passive"))
      (node (ref "T706") (pin "E") (pinfunction "E_E") (pintype "passive"))
      (node (ref "T707") (pin "E") (pinfunction "E_E") (pintype "passive"))
      (node (ref "T708") (pin "E") (pinfunction "E_E") (pintype "passive"))
      (node (ref "T709") (pin "E") (pinfunction "E_E") (pintype "passive"))
      (node (ref "T801") (pin "E") (pinfunction "E_E") (pintype "passive"))
      (node (ref "T802") (pin "E") (pinfunction "E_E") (pintype "passive"))
      (node (ref "T803") (pin "E") (pinfunction "E_E") (pintype "passive"))
      (node (ref "T804") (pin "E") (pinfunction "E_E") (pintype "passive"))
      (node (ref "T805") (pin "E") (pinfunction "E_E") (pintype "passive"))
      (node (ref "T806") (pin "E") (pinfunction "E_E") (pintype "passive"))
      (node (ref "T807") (pin "E") (pinfunction "E_E") (pintype "passive"))
      (node (ref "X1101") (pin "10") (pinfunction "10_10") (pintype "passive"))
      (node (ref "X1101") (pin "12") (pinfunction "12_12") (pintype "passive"))
      (node (ref "X1101") (pin "14") (pinfunction "14_14") (pintype "passive"))
      (node (ref "X1101") (pin "16") (pinfunction "16_16") (pintype "passive"))
      (node (ref "X1101") (pin "18") (pinfunction "18_18") (pintype "passive"))
      (node (ref "X1101") (pin "8") (pinfunction "8_8") (pintype "passive"))
    )
    (net (code "22") (name "Net-(D1001-PadA)") (class "Default")
      (node (ref "D1001") (pin "A") (pinfunction "A_A") (pintype "passive"))
      (node (ref "D1003") (pin "C") (pinfunction "C_C") (pintype "passive"))
      (node (ref "X1001") (pin "2") (pinfunction "2_2") (pintype "passive"))
    )
    (net (code "23") (name "Net-(D1002-PadA)") (class "Default")
      (node (ref "D1002") (pin "A") (pinfunction "A_A") (pintype "passive"))
      (node (ref "D1004") (pin "C") (pinfunction "C_C") (pintype "passive"))
      (node (ref "X1001") (pin "1") (pinfunction "1_1") (pintype "passive"))
    )
    (net (code "24") (name "Net-(IC101A-I0)") (class "Default")
      (node (ref "C102") (pin "1") (pinfunction "1_1") (pintype "passive"))
      (node (ref "IC101") (pin "1") (pinfunction "I0_1") (pintype "input"))
      (node (ref "IC101") (pin "2") (pinfunction "I1_2") (pintype "input"))
      (node (ref "R102") (pin "1") (pinfunction "1_1") (pintype "passive"))
    )
    (net (code "25") (name "Net-(IC101A-O)") (class "Default")
      (node (ref "IC101") (pin "3") (pinfunction "O_3") (pintype "output"))
      (node (ref "IC102") (pin "4") (pinfunction "I0_4") (pintype "input"))
      (node (ref "R102") (pin "2") (pinfunction "2_2") (pintype "passive"))
      (node (ref "TP101") (pin "1") (pinfunction "TP_1") (pintype "passive"))
    )
    (net (code "26") (name "Net-(IC101B-I0)") (class "Default")
      (node (ref "C101") (pin "+") (pinfunction "+_+") (pintype "passive"))
      (node (ref "IC101") (pin "5") (pinfunction "I0_5") (pintype "input"))
      (node (ref "IC101") (pin "6") (pinfunction "I1_6") (pintype "input"))
      (node (ref "R101") (pin "1") (pinfunction "1_1") (pintype "passive"))
    )
    (net (code "27") (name "Net-(IC101C-I0)") (class "Default")
      (node (ref "IC101") (pin "8") (pinfunction "I0_8") (pintype "input"))
      (node (ref "RN601") (pin "2") (pinfunction "2_2") (pintype "passive"))
      (node (ref "TP601") (pin "1") (pinfunction "TP_1") (pintype "passive"))
    )
    (net (code "28") (name "Net-(IC101C-I1)") (class "Default")
      (node (ref "IC101") (pin "9") (pinfunction "I1_9") (pintype "input"))
      (node (ref "RN601") (pin "4") (pinfunction "2_4") (pintype "passive"))
      (node (ref "TP602") (pin "1") (pinfunction "TP_1") (pintype "passive"))
    )
    (net (code "29") (name "Net-(IC101C-O)") (class "Default")
      (node (ref "IC101") (pin "10") (pinfunction "O_10") (pintype "output"))
      (node (ref "TP605") (pin "1") (pinfunction "TP_1") (pintype "passive"))
    )
    (net (code "30") (name "Net-(IC101D-I0)") (class "Default")
      (node (ref "IC101") (pin "12") (pinfunction "I0_12") (pintype "input"))
      (node (ref "RN601") (pin "6") (pinfunction "2_6") (pintype "passive"))
      (node (ref "TP603") (pin "1") (pinfunction "TP_1") (pintype "passive"))
    )
    (net (code "31") (name "Net-(IC101D-I1)") (class "Default")
      (node (ref "IC101") (pin "13") (pinfunction "I1_13") (pintype "input"))
      (node (ref "RN601") (pin "7") (pinfunction "1_7") (pintype "passive"))
      (node (ref "TP604") (pin "1") (pinfunction "TP_1") (pintype "passive"))
    )
    (net (code "32") (name "Net-(IC101D-O)") (class "Default")
      (node (ref "IC101") (pin "11") (pinfunction "O_11") (pintype "output"))
      (node (ref "TP606") (pin "1") (pinfunction "TP_1") (pintype "passive"))
    )
    (net (code "33") (name "Net-(IC102D-I1)") (class "Default")
      (node (ref "IC102") (pin "12") (pinfunction "I1_12") (pintype "input"))
      (node (ref "IC103") (pin "12") (pinfunction "CO_N_12") (pintype "output"))
    )
    (net (code "34") (name "Net-(IC201A-DS)") (class "Default")
      (node (ref "IC201") (pin "1") (pinfunction "DS_1") (pintype "input"))
      (node (ref "N201") (pin "2") (pinfunction "2_2") (pintype "passive"))
      (node (ref "TP201") (pin "1") (pinfunction "TP_1") (pintype "passive"))
    )
    (net (code "35") (name "Net-(IC201A-QA)") (class "Default")
      (node (ref "IC201") (pin "13") (pinfunction "QA_13") (pintype "output"))
      (node (ref "IC202") (pin "4") (pinfunction "DA_4") (pintype "input"))
    )
    (net (code "36") (name "Net-(IC201A-QB)") (class "Default")
      (node (ref "IC201") (pin "12") (pinfunction "QB_12") (pintype "output"))
      (node (ref "IC202") (pin "5") (pinfunction "DB_5") (pintype "input"))
    )
    (net (code "37") (name "Net-(IC201A-QC)") (class "Default")
      (node (ref "IC201") (pin "11") (pinfunction "QC_11") (pintype "output"))
      (node (ref "IC202") (pin "12") (pinfunction "DC_12") (pintype "input"))
    )
    (net (code "38") (name "Net-(IC301A-DS)") (class "Default")
      (node (ref "IC301") (pin "1") (pinfunction "DS_1") (pintype "input"))
      (node (ref "N301") (pin "2") (pinfunction "2_2") (pintype "passive"))
      (node (ref "TP301") (pin "1") (pinfunction "TP_1") (pintype "passive"))
    )
    (net (code "39") (name "Net-(IC301A-QA)") (class "Default")
      (node (ref "IC301") (pin "13") (pinfunction "QA_13") (pintype "output"))
      (node (ref "IC302") (pin "4") (pinfunction "DA_4") (pintype "input"))
    )
    (net (code "40") (name "Net-(IC301A-QB)") (class "Default")
      (node (ref "IC301") (pin "12") (pinfunction "QB_12") (pintype "output"))
      (node (ref "IC302") (pin "5") (pinfunction "DB_5") (pintype "input"))
    )
    (net (code "41") (name "Net-(IC301A-QC)") (class "Default")
      (node (ref "IC301") (pin "11") (pinfunction "QC_11") (pintype "output"))
      (node (ref "IC302") (pin "12") (pinfunction "DC_12") (pintype "input"))
    )
    (net (code "42") (name "Net-(IC401A-DS)") (class "Default")
      (node (ref "IC401") (pin "1") (pinfunction "DS_1") (pintype "input"))
      (node (ref "N401") (pin "2") (pinfunction "2_2") (pintype "passive"))
      (node (ref "TP401") (pin "1") (pinfunction "TP_1") (pintype "passive"))
    )
    (net (code "43") (name "Net-(IC401A-QA)") (class "Default")
      (node (ref "IC401") (pin "13") (pinfunction "QA_13") (pintype "output"))
      (node (ref "IC402") (pin "4") (pinfunction "DA_4") (pintype "input"))
    )
    (net (code "44") (name "Net-(IC401A-QB)") (class "Default")
      (node (ref "IC401") (pin "12") (pinfunction "QB_12") (pintype "output"))
      (node (ref "IC402") (pin "5") (pinfunction "DB_5") (pintype "input"))
    )
    (net (code "45") (name "Net-(IC401A-QC)") (class "Default")
      (node (ref "IC401") (pin "11") (pinfunction "QC_11") (pintype "output"))
      (node (ref "IC402") (pin "12") (pinfunction "DC_12") (pintype "input"))
    )
    (net (code "46") (name "Net-(IC501A-DS)") (class "Default")
      (node (ref "IC501") (pin "1") (pinfunction "DS_1") (pintype "input"))
      (node (ref "N501") (pin "2") (pinfunction "2_2") (pintype "passive"))
      (node (ref "TP501") (pin "1") (pinfunction "TP_1") (pintype "passive"))
    )
    (net (code "47") (name "Net-(IC501A-QA)") (class "Default")
      (node (ref "IC501") (pin "13") (pinfunction "QA_13") (pintype "output"))
      (node (ref "IC502") (pin "4") (pinfunction "DA_4") (pintype "input"))
    )
    (net (code "48") (name "Net-(IC501A-QB)") (class "Default")
      (node (ref "IC501") (pin "12") (pinfunction "QB_12") (pintype "output"))
      (node (ref "IC502") (pin "5") (pinfunction "DB_5") (pintype "input"))
    )
    (net (code "49") (name "Net-(IC501A-QC)") (class "Default")
      (node (ref "IC501") (pin "11") (pinfunction "QC_11") (pintype "output"))
      (node (ref "IC502") (pin "12") (pinfunction "DC_12") (pintype "input"))
    )
    (net (code "50") (name "Net-(IC501A-QD)") (class "Default")
      (node (ref "IC501") (pin "10") (pinfunction "QD_10") (pintype "output"))
      (node (ref "IC502") (pin "13") (pinfunction "DD_13") (pintype "input"))
    )
    (net (code "51") (name "Net-(IC901-DSCHRG)") (class "Default")
      (node (ref "D901") (pin "A") (pinfunction "A_A") (pintype "passive"))
      (node (ref "IC901") (pin "7") (pinfunction "DSCHRG_7") (pintype "output"))
      (node (ref "R901") (pin "2") (pinfunction "2_2") (pintype "passive"))
      (node (ref "R902") (pin "1") (pinfunction "1_1") (pintype "passive"))
      (node (ref "R904") (pin "B") (pinfunction "B_B") (pintype "passive"))
      (node (ref "RPH901") (pin "2") (pinfunction "2_2") (pintype "passive"))
    )
    (net (code "52") (name "Net-(IC901-OC)") (class "Default")
      (node (ref "C903") (pin "1") (pinfunction "1_1") (pintype "passive"))
      (node (ref "IC901") (pin "4") (pinfunction "RST#_4") (pintype "input"))
      (node (ref "IC901") (pin "5") (pinfunction "OC_5") (pintype "passive"))
    )
    (net (code "53") (name "Net-(IC901-TRG)") (class "Default")
      (node (ref "C902") (pin "1") (pinfunction "1_1") (pintype "passive"))
      (node (ref "D901") (pin "C") (pinfunction "C_C") (pintype "passive"))
      (node (ref "IC901") (pin "2") (pinfunction "TRG_2") (pintype "passive"))
      (node (ref "IC901") (pin "6") (pinfunction "TRSHLD_6") (pintype "passive"))
      (node (ref "R901") (pin "1") (pinfunction "1_1") (pintype "passive"))
    )
    (net (code "54") (name "Net-(IC1001-IN)") (class "Default")
      (node (ref "C1001") (pin "+") (pinfunction "+_+") (pintype "passive"))
      (node (ref "C1002") (pin "1") (pinfunction "1_1") (pintype "passive"))
      (node (ref "D1001") (pin "C") (pinfunction "C_C") (pintype "passive"))
      (node (ref "D1002") (pin "C") (pinfunction "C_C") (pintype "passive"))
      (node (ref "IC1001") (pin "1") (pinfunction "IN_1") (pintype "power_in"))
    )
    (net (code "55") (name "Net-(J1001-Pad2)") (class "Default")
      (node (ref "J1001") (pin "2") (pinfunction "2_2") (pintype "passive"))
      (node (ref "R1001") (pin "1") (pinfunction "1_1") (pintype "passive"))
    )
    (net (code "56") (name "Net-(LED701-PadA)") (class "Default")
      (node (ref "LED701") (pin "A") (pinfunction "A_A") (pintype "passive"))
      (node (ref "R704") (pin "2") (pinfunction "2_2") (pintype "passive"))
    )
    (net (code "57") (name "Net-(LED702-PadA)") (class "Default")
      (node (ref "LED702") (pin "A") (pinfunction "A_A") (pintype "passive"))
      (node (ref "R705") (pin "2") (pinfunction "2_2") (pintype "passive"))
    )
    (net (code "58") (name "Net-(LED703-PadA)") (class "Default")
      (node (ref "LED703") (pin "A") (pinfunction "A_A") (pintype "passive"))
      (node (ref "R706") (pin "2") (pinfunction "2_2") (pintype "passive"))
    )
    (net (code "59") (name "Net-(LED704-PadA)") (class "Default")
      (node (ref "LED704") (pin "A") (pinfunction "A_A") (pintype "passive"))
      (node (ref "R710") (pin "2") (pinfunction "2_2") (pintype "passive"))
    )
    (net (code "60") (name "Net-(LED705-PadA)") (class "Default")
      (node (ref "LED705") (pin "A") (pinfunction "A_A") (pintype "passive"))
      (node (ref "R711") (pin "2") (pinfunction "2_2") (pintype "passive"))
    )
    (net (code "61") (name "Net-(LED706-PadA)") (class "Default")
      (node (ref "LED706") (pin "A") (pinfunction "A_A") (pintype "passive"))
      (node (ref "R712") (pin "2") (pinfunction "2_2") (pintype "passive"))
    )
    (net (code "62") (name "Net-(LED707-PadA)") (class "Default")
      (node (ref "LED707") (pin "A") (pinfunction "A_A") (pintype "passive"))
      (node (ref "R716") (pin "2") (pinfunction "2_2") (pintype "passive"))
    )
    (net (code "63") (name "Net-(LED708-PadA)") (class "Default")
      (node (ref "LED708") (pin "A") (pinfunction "A_A") (pintype "passive"))
      (node (ref "R717") (pin "2") (pinfunction "2_2") (pintype "passive"))
    )
    (net (code "64") (name "Net-(LED709-PadA)") (class "Default")
      (node (ref "LED709") (pin "A") (pinfunction "A_A") (pintype "passive"))
      (node (ref "R718") (pin "2") (pinfunction "2_2") (pintype "passive"))
    )
    (net (code "65") (name "Net-(LED801-PadA)") (class "Default")
      (node (ref "LED801") (pin "A") (pinfunction "A_A") (pintype "passive"))
      (node (ref "R804") (pin "2") (pinfunction "2_2") (pintype "passive"))
    )
    (net (code "66") (name "Net-(LED802-PadA)") (class "Default")
      (node (ref "LED802") (pin "A") (pinfunction "A_A") (pintype "passive"))
      (node (ref "R805") (pin "2") (pinfunction "2_2") (pintype "passive"))
    )
    (net (code "67") (name "Net-(LED803-PadA)") (class "Default")
      (node (ref "LED803") (pin "A") (pinfunction "A_A") (pintype "passive"))
      (node (ref "R806") (pin "2") (pinfunction "2_2") (pintype "passive"))
    )
    (net (code "68") (name "Net-(LED804-PadA)") (class "Default")
      (node (ref "LED804") (pin "A") (pinfunction "A_A") (pintype "passive"))
      (node (ref "R810") (pin "2") (pinfunction "2_2") (pintype "passive"))
    )
    (net (code "69") (name "Net-(LED805-PadA)") (class "Default")
      (node (ref "LED805") (pin "A") (pinfunction "A_A") (pintype "passive"))
      (node (ref "R811") (pin "2") (pinfunction "2_2") (pintype "passive"))
    )
    (net (code "70") (name "Net-(LED806-PadA)") (class "Default")
      (node (ref "LED806") (pin "A") (pinfunction "A_A") (pintype "passive"))
      (node (ref "R812") (pin "2") (pinfunction "2_2") (pintype "passive"))
    )
    (net (code "71") (name "Net-(LED807-PadA)") (class "Default")
      (node (ref "LED807") (pin "A") (pinfunction "A_A") (pintype "passive"))
      (node (ref "R814") (pin "2") (pinfunction "2_2") (pintype "passive"))
    )
    (net (code "72") (name "Net-(LED1001-PadA)") (class "Default")
      (node (ref "LED1001") (pin "A") (pinfunction "A_A") (pintype "passive"))
      (node (ref "R1001") (pin "2") (pinfunction "2_2") (pintype "passive"))
    )
    (net (code "73") (name "Net-(N701-Pad2)") (class "Default")
      (node (ref "N701") (pin "2") (pinfunction "2_2") (pintype "passive"))
      (node (ref "R701") (pin "1") (pinfunction "1_1") (pintype "passive"))
    )
    (net (code "74") (name "Net-(N702-Pad2)") (class "Default")
      (node (ref "N702") (pin "2") (pinfunction "2_2") (pintype "passive"))
      (node (ref "R702") (pin "1") (pinfunction "1_1") (pintype "passive"))
    )
    (net (code "75") (name "Net-(N703-Pad2)") (class "Default")
      (node (ref "N703") (pin "2") (pinfunction "2_2") (pintype "passive"))
      (node (ref "R703") (pin "1") (pinfunction "1_1") (pintype "passive"))
    )
    (net (code "76") (name "Net-(N704-Pad2)") (class "Default")
      (node (ref "N704") (pin "2") (pinfunction "2_2") (pintype "passive"))
      (node (ref "R707") (pin "1") (pinfunction "1_1") (pintype "passive"))
    )
    (net (code "77") (name "Net-(N705-Pad2)") (class "Default")
      (node (ref "N705") (pin "2") (pinfunction "2_2") (pintype "passive"))
      (node (ref "R708") (pin "1") (pinfunction "1_1") (pintype "passive"))
    )
    (net (code "78") (name "Net-(N706-Pad2)") (class "Default")
      (node (ref "N706") (pin "2") (pinfunction "2_2") (pintype "passive"))
      (node (ref "R709") (pin "1") (pinfunction "1_1") (pintype "passive"))
    )
    (net (code "79") (name "Net-(N707-Pad2)") (class "Default")
      (node (ref "N707") (pin "2") (pinfunction "2_2") (pintype "passive"))
      (node (ref "R713") (pin "1") (pinfunction "1_1") (pintype "passive"))
    )
    (net (code "80") (name "Net-(N708-Pad2)") (class "Default")
      (node (ref "N708") (pin "2") (pinfunction "2_2") (pintype "passive"))
      (node (ref "R714") (pin "1") (pinfunction "1_1") (pintype "passive"))
    )
    (net (code "81") (name "Net-(N709-Pad2)") (class "Default")
      (node (ref "N709") (pin "2") (pinfunction "2_2") (pintype "passive"))
      (node (ref "R715") (pin "1") (pinfunction "1_1") (pintype "passive"))
    )
    (net (code "82") (name "Net-(N801-Pad2)") (class "Default")
      (node (ref "N801") (pin "2") (pinfunction "2_2") (pintype "passive"))
      (node (ref "R801") (pin "1") (pinfunction "1_1") (pintype "passive"))
    )
    (net (code "83") (name "Net-(N802-Pad2)") (class "Default")
      (node (ref "N802") (pin "2") (pinfunction "2_2") (pintype "passive"))
      (node (ref "R802") (pin "1") (pinfunction "1_1") (pintype "passive"))
    )
    (net (code "84") (name "Net-(N803-Pad2)") (class "Default")
      (node (ref "N803") (pin "2") (pinfunction "2_2") (pintype "passive"))
      (node (ref "R803") (pin "1") (pinfunction "1_1") (pintype "passive"))
    )
    (net (code "85") (name "Net-(N804-Pad2)") (class "Default")
      (node (ref "N804") (pin "2") (pinfunction "2_2") (pintype "passive"))
      (node (ref "R807") (pin "1") (pinfunction "1_1") (pintype "passive"))
    )
    (net (code "86") (name "Net-(N805-Pad2)") (class "Default")
      (node (ref "N805") (pin "2") (pinfunction "2_2") (pintype "passive"))
      (node (ref "R808") (pin "1") (pinfunction "1_1") (pintype "passive"))
    )
    (net (code "87") (name "Net-(N806-Pad2)") (class "Default")
      (node (ref "N806") (pin "2") (pinfunction "2_2") (pintype "passive"))
      (node (ref "R809") (pin "1") (pinfunction "1_1") (pintype "passive"))
    )
    (net (code "88") (name "Net-(N807-Pad2)") (class "Default")
      (node (ref "N807") (pin "2") (pinfunction "2_2") (pintype "passive"))
      (node (ref "R813") (pin "1") (pinfunction "1_1") (pintype "passive"))
    )
    (net (code "89") (name "Net-(R101-Pad2)") (class "Default")
      (node (ref "R101") (pin "2") (pinfunction "2_2") (pintype "passive"))
      (node (ref "R103") (pin "A") (pinfunction "A_A") (pintype "passive"))
      (node (ref "R103") (pin "W") (pinfunction "W_W") (pintype "passive"))
    )
    (net (code "90") (name "Net-(R701-Pad2)") (class "Default")
      (node (ref "R701") (pin "2") (pinfunction "2_2") (pintype "passive"))
      (node (ref "T701") (pin "B") (pinfunction "B_B") (pintype "passive"))
    )
    (net (code "91") (name "Net-(R702-Pad2)") (class "Default")
      (node (ref "R702") (pin "2") (pinfunction "2_2") (pintype "passive"))
      (node (ref "T702") (pin "B") (pinfunction "B_B") (pintype "passive"))
    )
    (net (code "92") (name "Net-(R703-Pad2)") (class "Default")
      (node (ref "R703") (pin "2") (pinfunction "2_2") (pintype "passive"))
      (node (ref "T703") (pin "B") (pinfunction "B_B") (pintype "passive"))
    )
    (net (code "93") (name "Net-(R707-Pad2)") (class "Default")
      (node (ref "R707") (pin "2") (pinfunction "2_2") (pintype "passive"))
      (node (ref "T704") (pin "B") (pinfunction "B_B") (pintype "passive"))
    )
    (net (code "94") (name "Net-(R708-Pad2)") (class "Default")
      (node (ref "R708") (pin "2") (pinfunction "2_2") (pintype "passive"))
      (node (ref "T705") (pin "B") (pinfunction "B_B") (pintype "passive"))
    )
    (net (code "95") (name "Net-(R709-Pad2)") (class "Default")
      (node (ref "R709") (pin "2") (pinfunction "2_2") (pintype "passive"))
      (node (ref "T706") (pin "B") (pinfunction "B_B") (pintype "passive"))
    )
    (net (code "96") (name "Net-(R713-Pad2)") (class "Default")
      (node (ref "R713") (pin "2") (pinfunction "2_2") (pintype "passive"))
      (node (ref "T707") (pin "B") (pinfunction "B_B") (pintype "passive"))
    )
    (net (code "97") (name "Net-(R714-Pad2)") (class "Default")
      (node (ref "R714") (pin "2") (pinfunction "2_2") (pintype "passive"))
      (node (ref "T708") (pin "B") (pinfunction "B_B") (pintype "passive"))
    )
    (net (code "98") (name "Net-(R715-Pad2)") (class "Default")
      (node (ref "R715") (pin "2") (pinfunction "2_2") (pintype "passive"))
      (node (ref "T709") (pin "B") (pinfunction "B_B") (pintype "passive"))
    )
    (net (code "99") (name "Net-(R801-Pad2)") (class "Default")
      (node (ref "R801") (pin "2") (pinfunction "2_2") (pintype "passive"))
      (node (ref "T801") (pin "B") (pinfunction "B_B") (pintype "passive"))
    )
    (net (code "100") (name "Net-(R802-Pad2)") (class "Default")
      (node (ref "R802") (pin "2") (pinfunction "2_2") (pintype "passive"))
      (node (ref "T802") (pin "B") (pinfunction "B_B") (pintype "passive"))
    )
    (net (code "101") (name "Net-(R803-Pad2)") (class "Default")
      (node (ref "R803") (pin "2") (pinfunction "2_2") (pintype "passive"))
      (node (ref "T803") (pin "B") (pinfunction "B_B") (pintype "passive"))
    )
    (net (code "102") (name "Net-(R807-Pad2)") (class "Default")
      (node (ref "R807") (pin "2") (pinfunction "2_2") (pintype "passive"))
      (node (ref "T804") (pin "B") (pinfunction "B_B") (pintype "passive"))
    )
    (net (code "103") (name "Net-(R808-Pad2)") (class "Default")
      (node (ref "R808") (pin "2") (pinfunction "2_2") (pintype "passive"))
      (node (ref "T805") (pin "B") (pinfunction "B_B") (pintype "passive"))
    )
    (net (code "104") (name "Net-(R809-Pad2)") (class "Default")
      (node (ref "R809") (pin "2") (pinfunction "2_2") (pintype "passive"))
      (node (ref "T806") (pin "B") (pinfunction "B_B") (pintype "passive"))
    )
    (net (code "105") (name "Net-(R813-Pad2)") (class "Default")
      (node (ref "R813") (pin "2") (pinfunction "2_2") (pintype "passive"))
      (node (ref "T807") (pin "B") (pinfunction "B_B") (pintype "passive"))
    )
    (net (code "106") (name "Net-(R903-Pad1)") (class "Default")
      (node (ref "R903") (pin "1") (pinfunction "1_1") (pintype "passive"))
      (node (ref "R904") (pin "A") (pinfunction "A_A") (pintype "passive"))
      (node (ref "R904") (pin "W") (pinfunction "W_W") (pintype "passive"))
      (node (ref "RPH901") (pin "1") (pinfunction "1_1") (pintype "passive"))
    )
    (net (code "107") (name "Net-(R906-Pad2)") (class "Default")
      (node (ref "R906") (pin "2") (pinfunction "2_2") (pintype "passive"))
      (node (ref "T901") (pin "B") (pinfunction "B_B") (pintype "passive"))
    )
    (net (code "108") (name "P5V") (class "Default")
      (node (ref "C1003") (pin "1") (pinfunction "1_1") (pintype "passive"))
      (node (ref "C103") (pin "1") (pinfunction "1_1") (pintype "passive"))
      (node (ref "C104") (pin "1") (pinfunction "1_1") (pintype "passive"))
      (node (ref "C105") (pin "1") (pinfunction "1_1") (pintype "passive"))
      (node (ref "C201") (pin "1") (pinfunction "1_1") (pintype "passive"))
      (node (ref "C202") (pin "1") (pinfunction "1_1") (pintype "passive"))
      (node (ref "C301") (pin "1") (pinfunction "1_1") (pintype "passive"))
      (node (ref "C302") (pin "1") (pinfunction "1_1") (pintype "passive"))
      (node (ref "C401") (pin "1") (pinfunction "1_1") (pintype "passive"))
      (node (ref "C402") (pin "1") (pinfunction "1_1") (pintype "passive"))
      (node (ref "C501") (pin "1") (pinfunction "1_1") (pintype "passive"))
      (node (ref "C502") (pin "1") (pinfunction "1_1") (pintype "passive"))
      (node (ref "C901") (pin "1") (pinfunction "1_1") (pintype "passive"))
      (node (ref "IC1001") (pin "3") (pinfunction "OUT_3") (pintype "power_in"))
      (node (ref "IC101") (pin "14") (pinfunction "VCC_14") (pintype "power_in"))
      (node (ref "IC102") (pin "13") (pinfunction "I0_13") (pintype "input"))
      (node (ref "IC102") (pin "14") (pinfunction "VCC_14") (pintype "power_in"))
      (node (ref "IC102") (pin "2") (pinfunction "I1_2") (pintype "input"))
      (node (ref "IC102") (pin "5") (pinfunction "I1_5") (pintype "input"))
      (node (ref "IC102") (pin "9") (pinfunction "I1_9") (pintype "input"))
      (node (ref "IC103") (pin "11") (pinfunction "LD_N_11") (pintype "input"))
      (node (ref "IC103") (pin "16") (pinfunction "VCC_16") (pintype "power_in"))
      (node (ref "IC103") (pin "4") (pinfunction "DOWN_4") (pintype "input"))
      (node (ref "IC201") (pin "14") (pinfunction "VCC_14") (pintype "power_in"))
      (node (ref "IC202") (pin "1") (pinfunction "CLR_N_1") (pintype "input"))
      (node (ref "IC202") (pin "16") (pinfunction "VCC_16") (pintype "power_in"))
      (node (ref "IC301") (pin "14") (pinfunction "VCC_14") (pintype "power_in"))
      (node (ref "IC302") (pin "1") (pinfunction "CLR_N_1") (pintype "input"))
      (node (ref "IC302") (pin "16") (pinfunction "VCC_16") (pintype "power_in"))
      (node (ref "IC401") (pin "14") (pinfunction "VCC_14") (pintype "power_in"))
      (node (ref "IC402") (pin "1") (pinfunction "CLR_N_1") (pintype "input"))
      (node (ref "IC402") (pin "16") (pinfunction "VCC_16") (pintype "power_in"))
      (node (ref "IC501") (pin "14") (pinfunction "VCC_14") (pintype "power_in"))
      (node (ref "IC502") (pin "1") (pinfunction "CLR_N_1") (pintype "input"))
      (node (ref "IC502") (pin "16") (pinfunction "VCC_16") (pintype "power_in"))
      (node (ref "IC901") (pin "8") (pinfunction "VCC_8") (pintype "power_in"))
      (node (ref "J1001") (pin "1") (pinfunction "1_1") (pintype "passive"))
      (node (ref "R902") (pin "2") (pinfunction "2_2") (pintype "passive"))
      (node (ref "R903") (pin "2") (pinfunction "2_2") (pintype "passive"))
      (node (ref "R905") (pin "2") (pinfunction "2_2") (pintype "passive"))
      (node (ref "RN601") (pin "1") (pinfunction "1_1") (pintype "passive"))
      (node (ref "RN601") (pin "3") (pinfunction "1_3") (pintype "passive"))
      (node (ref "RN601") (pin "5") (pinfunction "1_5") (pintype "passive"))
      (node (ref "RN601") (pin "8") (pinfunction "2_8") (pintype "passive"))
      (node (ref "T901") (pin "E") (pinfunction "E_E") (pintype "passive"))
      (node (ref "X1101") (pin "20") (pinfunction "20_20") (pintype "passive"))
      (node (ref "X1101") (pin "22") (pinfunction "22_22") (pintype "passive"))
      (node (ref "X1101") (pin "24") (pinfunction "24_24") (pintype "passive"))
      (node (ref "X1101") (pin "26") (pinfunction "26_26") (pintype "passive"))
    )
    (net (code "109") (name "REG_1_QA") (class "Default")
      (node (ref "IC202") (pin "2") (pinfunction "QA_2") (pintype "output"))
      (node (ref "N708") (pin "1") (pinfunction "1_1") (pintype "passive"))
    )
    (net (code "110") (name "REG_1_QB") (class "Default")
      (node (ref "IC202") (pin "7") (pinfunction "QB_7") (pintype "output"))
      (node (ref "N707") (pin "1") (pinfunction "1_1") (pintype "passive"))
    )
    (net (code "111") (name "REG_1_QC") (class "Default")
      (node (ref "IC202") (pin "10") (pinfunction "QC_10") (pintype "output"))
      (node (ref "N706") (pin "1") (pinfunction "1_1") (pintype "passive"))
    )
    (net (code "112") (name "REG_1_QD") (class "Default")
      (node (ref "IC202") (pin "15") (pinfunction "QD_15") (pintype "output"))
      (node (ref "N705") (pin "1") (pinfunction "1_1") (pintype "passive"))
    )
    (net (code "113") (name "REG_2_QA") (class "Default")
      (node (ref "IC302") (pin "2") (pinfunction "QA_2") (pintype "output"))
      (node (ref "N704") (pin "1") (pinfunction "1_1") (pintype "passive"))
    )
    (net (code "114") (name "REG_2_QB") (class "Default")
      (node (ref "IC302") (pin "7") (pinfunction "QB_7") (pintype "output"))
      (node (ref "N703") (pin "1") (pinfunction "1_1") (pintype "passive"))
    )
    (net (code "115") (name "REG_2_QC") (class "Default")
      (node (ref "IC302") (pin "10") (pinfunction "QC_10") (pintype "output"))
      (node (ref "N702") (pin "1") (pinfunction "1_1") (pintype "passive"))
    )
    (net (code "116") (name "REG_2_QD") (class "Default")
      (node (ref "IC302") (pin "15") (pinfunction "QD_15") (pintype "output"))
      (node (ref "N701") (pin "1") (pinfunction "1_1") (pintype "passive"))
    )
    (net (code "117") (name "REG_3_QA") (class "Default")
      (node (ref "IC402") (pin "2") (pinfunction "QA_2") (pintype "output"))
      (node (ref "N804") (pin "1") (pinfunction "1_1") (pintype "passive"))
    )
    (net (code "118") (name "REG_3_QB") (class "Default")
      (node (ref "IC402") (pin "7") (pinfunction "QB_7") (pintype "output"))
      (node (ref "N805") (pin "1") (pinfunction "1_1") (pintype "passive"))
    )
    (net (code "119") (name "REG_3_QC") (class "Default")
      (node (ref "IC402") (pin "10") (pinfunction "QC_10") (pintype "output"))
      (node (ref "N806") (pin "1") (pinfunction "1_1") (pintype "passive"))
    )
    (net (code "120") (name "REG_3_QD") (class "Default")
      (node (ref "IC402") (pin "15") (pinfunction "QD_15") (pintype "output"))
      (node (ref "N807") (pin "1") (pinfunction "1_1") (pintype "passive"))
    )
    (net (code "121") (name "REG_4_QA") (class "Default")
      (node (ref "IC502") (pin "2") (pinfunction "QA_2") (pintype "output"))
      (node (ref "N709") (pin "1") (pinfunction "1_1") (pintype "passive"))
    )
    (net (code "122") (name "REG_4_QB") (class "Default")
      (node (ref "IC502") (pin "7") (pinfunction "QB_7") (pintype "output"))
      (node (ref "N801") (pin "1") (pinfunction "1_1") (pintype "passive"))
    )
    (net (code "123") (name "REG_4_QC") (class "Default")
      (node (ref "IC502") (pin "10") (pinfunction "QC_10") (pintype "output"))
      (node (ref "N802") (pin "1") (pinfunction "1_1") (pintype "passive"))
    )
    (net (code "124") (name "REG_4_QD") (class "Default")
      (node (ref "IC502") (pin "15") (pinfunction "QD_15") (pintype "output"))
      (node (ref "N803") (pin "1") (pinfunction "1_1") (pintype "passive"))
    )
    (net (code "125") (name "REG_LOAD") (class "Default")
      (node (ref "IC102") (pin "11") (pinfunction "O_11") (pintype "output"))
      (node (ref "IC202") (pin "9") (pinfunction "CLK_9") (pintype "input"))
      (node (ref "IC302") (pin "9") (pinfunction "CLK_9") (pintype "input"))
      (node (ref "IC402") (pin "9") (pinfunction "CLK_9") (pintype "input"))
      (node (ref "IC502") (pin "9") (pinfunction "CLK_9") (pintype "input"))
      (node (ref "TP105") (pin "1") (pinfunction "TP_1") (pintype "passive"))
    )
    (net (code "126") (name "SH_1_QD") (class "Default")
      (node (ref "IC201") (pin "10") (pinfunction "QD_10") (pintype "output"))
      (node (ref "IC202") (pin "13") (pinfunction "DD_13") (pintype "input"))
      (node (ref "N301") (pin "1") (pinfunction "1_1") (pintype "passive"))
    )
    (net (code "127") (name "SH_2_QD") (class "Default")
      (node (ref "IC301") (pin "10") (pinfunction "QD_10") (pintype "output"))
      (node (ref "IC302") (pin "13") (pinfunction "DD_13") (pintype "input"))
      (node (ref "N401") (pin "1") (pinfunction "1_1") (pintype "passive"))
    )
    (net (code "128") (name "SH_3_QD") (class "Default")
      (node (ref "IC401") (pin "10") (pinfunction "QD_10") (pintype "output"))
      (node (ref "IC402") (pin "13") (pinfunction "DD_13") (pintype "input"))
      (node (ref "N501") (pin "1") (pinfunction "1_1") (pintype "passive"))
    )
    (net (code "129") (name "TIM_OUT") (class "Default")
      (node (ref "IC901") (pin "3") (pinfunction "OUT_3") (pintype "output"))
      (node (ref "R905") (pin "1") (pinfunction "1_1") (pintype "passive"))
      (node (ref "R906") (pin "1") (pinfunction "1_1") (pintype "passive"))
    )
    (net (code "130") (name "V_LED") (class "Default")
      (node (ref "R704") (pin "1") (pinfunction "1_1") (pintype "passive"))
      (node (ref "R705") (pin "1") (pinfunction "1_1") (pintype "passive"))
      (node (ref "R706") (pin "1") (pinfunction "1_1") (pintype "passive"))
      (node (ref "R710") (pin "1") (pinfunction "1_1") (pintype "passive"))
      (node (ref "R711") (pin "1") (pinfunction "1_1") (pintype "passive"))
      (node (ref "R712") (pin "1") (pinfunction "1_1") (pintype "passive"))
      (node (ref "R716") (pin "1") (pinfunction "1_1") (pintype "passive"))
      (node (ref "R717") (pin "1") (pinfunction "1_1") (pintype "passive"))
      (node (ref "R718") (pin "1") (pinfunction "1_1") (pintype "passive"))
      (node (ref "R804") (pin "1") (pinfunction "1_1") (pintype "passive"))
      (node (ref "R805") (pin "1") (pinfunction "1_1") (pintype "passive"))
      (node (ref "R806") (pin "1") (pinfunction "1_1") (pintype "passive"))
      (node (ref "R810") (pin "1") (pinfunction "1_1") (pintype "passive"))
      (node (ref "R811") (pin "1") (pinfunction "1_1") (pintype "passive"))
      (node (ref "R812") (pin "1") (pinfunction "1_1") (pintype "passive"))
      (node (ref "R814") (pin "1") (pinfunction "1_1") (pintype "passive"))
      (node (ref "T901") (pin "C") (pinfunction "C_C") (pintype "passive"))
    )
    (net (code "131") (name "unconnected-(H601-MOUNT-PadH1)") (class "Default")
      (node (ref "H601") (pin "H1") (pinfunction "MOUNT_H1") (pintype "passive"))
    )
    (net (code "132") (name "unconnected-(H602-MOUNT-PadH1)") (class "Default")
      (node (ref "H602") (pin "H1") (pinfunction "MOUNT_H1") (pintype "passive"))
    )
    (net (code "133") (name "unconnected-(H603-MOUNT-PadH1)") (class "Default")
      (node (ref "H603") (pin "H1") (pinfunction "MOUNT_H1") (pintype "passive"))
    )
    (net (code "134") (name "unconnected-(H604-MOUNT-PadH1)") (class "Default")
      (node (ref "H604") (pin "H1") (pinfunction "MOUNT_H1") (pintype "passive"))
    )
    (net (code "135") (name "unconnected-(IC103A-BO_N-Pad13)") (class "Default")
      (node (ref "IC103") (pin "13") (pinfunction "BO_N_13") (pintype "output"))
    )
    (net (code "136") (name "unconnected-(IC103A-QA-Pad3)") (class "Default")
      (node (ref "IC103") (pin "3") (pinfunction "QA_3") (pintype "output"))
    )
    (net (code "137") (name "unconnected-(IC103A-QB-Pad2)") (class "Default")
      (node (ref "IC103") (pin "2") (pinfunction "QB_2") (pintype "output"))
    )
    (net (code "138") (name "unconnected-(IC103A-QC-Pad6)") (class "Default")
      (node (ref "IC103") (pin "6") (pinfunction "QC_6") (pintype "output"))
    )
    (net (code "139") (name "unconnected-(IC103A-QD-Pad7)") (class "Default")
      (node (ref "IC103") (pin "7") (pinfunction "QD_7") (pintype "output"))
    )
    (net (code "140") (name "unconnected-(IC202A-QA_N-Pad3)") (class "Default")
      (node (ref "IC202") (pin "3") (pinfunction "QA_N_3") (pintype "output"))
    )
    (net (code "141") (name "unconnected-(IC202A-QB_N-Pad6)") (class "Default")
      (node (ref "IC202") (pin "6") (pinfunction "QB_N_6") (pintype "output"))
    )
    (net (code "142") (name "unconnected-(IC202A-QC_N-Pad11)") (class "Default")
      (node (ref "IC202") (pin "11") (pinfunction "QC_N_11") (pintype "output"))
    )
    (net (code "143") (name "unconnected-(IC202A-QD_N-Pad14)") (class "Default")
      (node (ref "IC202") (pin "14") (pinfunction "QD_N_14") (pintype "output"))
    )
    (net (code "144") (name "unconnected-(IC302A-QA_N-Pad3)") (class "Default")
      (node (ref "IC302") (pin "3") (pinfunction "QA_N_3") (pintype "output"))
    )
    (net (code "145") (name "unconnected-(IC302A-QB_N-Pad6)") (class "Default")
      (node (ref "IC302") (pin "6") (pinfunction "QB_N_6") (pintype "output"))
    )
    (net (code "146") (name "unconnected-(IC302A-QC_N-Pad11)") (class "Default")
      (node (ref "IC302") (pin "11") (pinfunction "QC_N_11") (pintype "output"))
    )
    (net (code "147") (name "unconnected-(IC302A-QD_N-Pad14)") (class "Default")
      (node (ref "IC302") (pin "14") (pinfunction "QD_N_14") (pintype "output"))
    )
    (net (code "148") (name "unconnected-(IC402A-QA_N-Pad3)") (class "Default")
      (node (ref "IC402") (pin "3") (pinfunction "QA_N_3") (pintype "output"))
    )
    (net (code "149") (name "unconnected-(IC402A-QB_N-Pad6)") (class "Default")
      (node (ref "IC402") (pin "6") (pinfunction "QB_N_6") (pintype "output"))
    )
    (net (code "150") (name "unconnected-(IC402A-QC_N-Pad11)") (class "Default")
      (node (ref "IC402") (pin "11") (pinfunction "QC_N_11") (pintype "output"))
    )
    (net (code "151") (name "unconnected-(IC402A-QD_N-Pad14)") (class "Default")
      (node (ref "IC402") (pin "14") (pinfunction "QD_N_14") (pintype "output"))
    )
    (net (code "152") (name "unconnected-(IC502A-QA_N-Pad3)") (class "Default")
      (node (ref "IC502") (pin "3") (pinfunction "QA_N_3") (pintype "output"))
    )
    (net (code "153") (name "unconnected-(IC502A-QB_N-Pad6)") (class "Default")
      (node (ref "IC502") (pin "6") (pinfunction "QB_N_6") (pintype "output"))
    )
    (net (code "154") (name "unconnected-(IC502A-QC_N-Pad11)") (class "Default")
      (node (ref "IC502") (pin "11") (pinfunction "QC_N_11") (pintype "output"))
    )
    (net (code "155") (name "unconnected-(IC502A-QD_N-Pad14)") (class "Default")
      (node (ref "IC502") (pin "14") (pinfunction "QD_N_14") (pintype "output"))
    )
  )
)
